# BMS_24.net
KiCad netlist of a schematic drawn in EAGLE
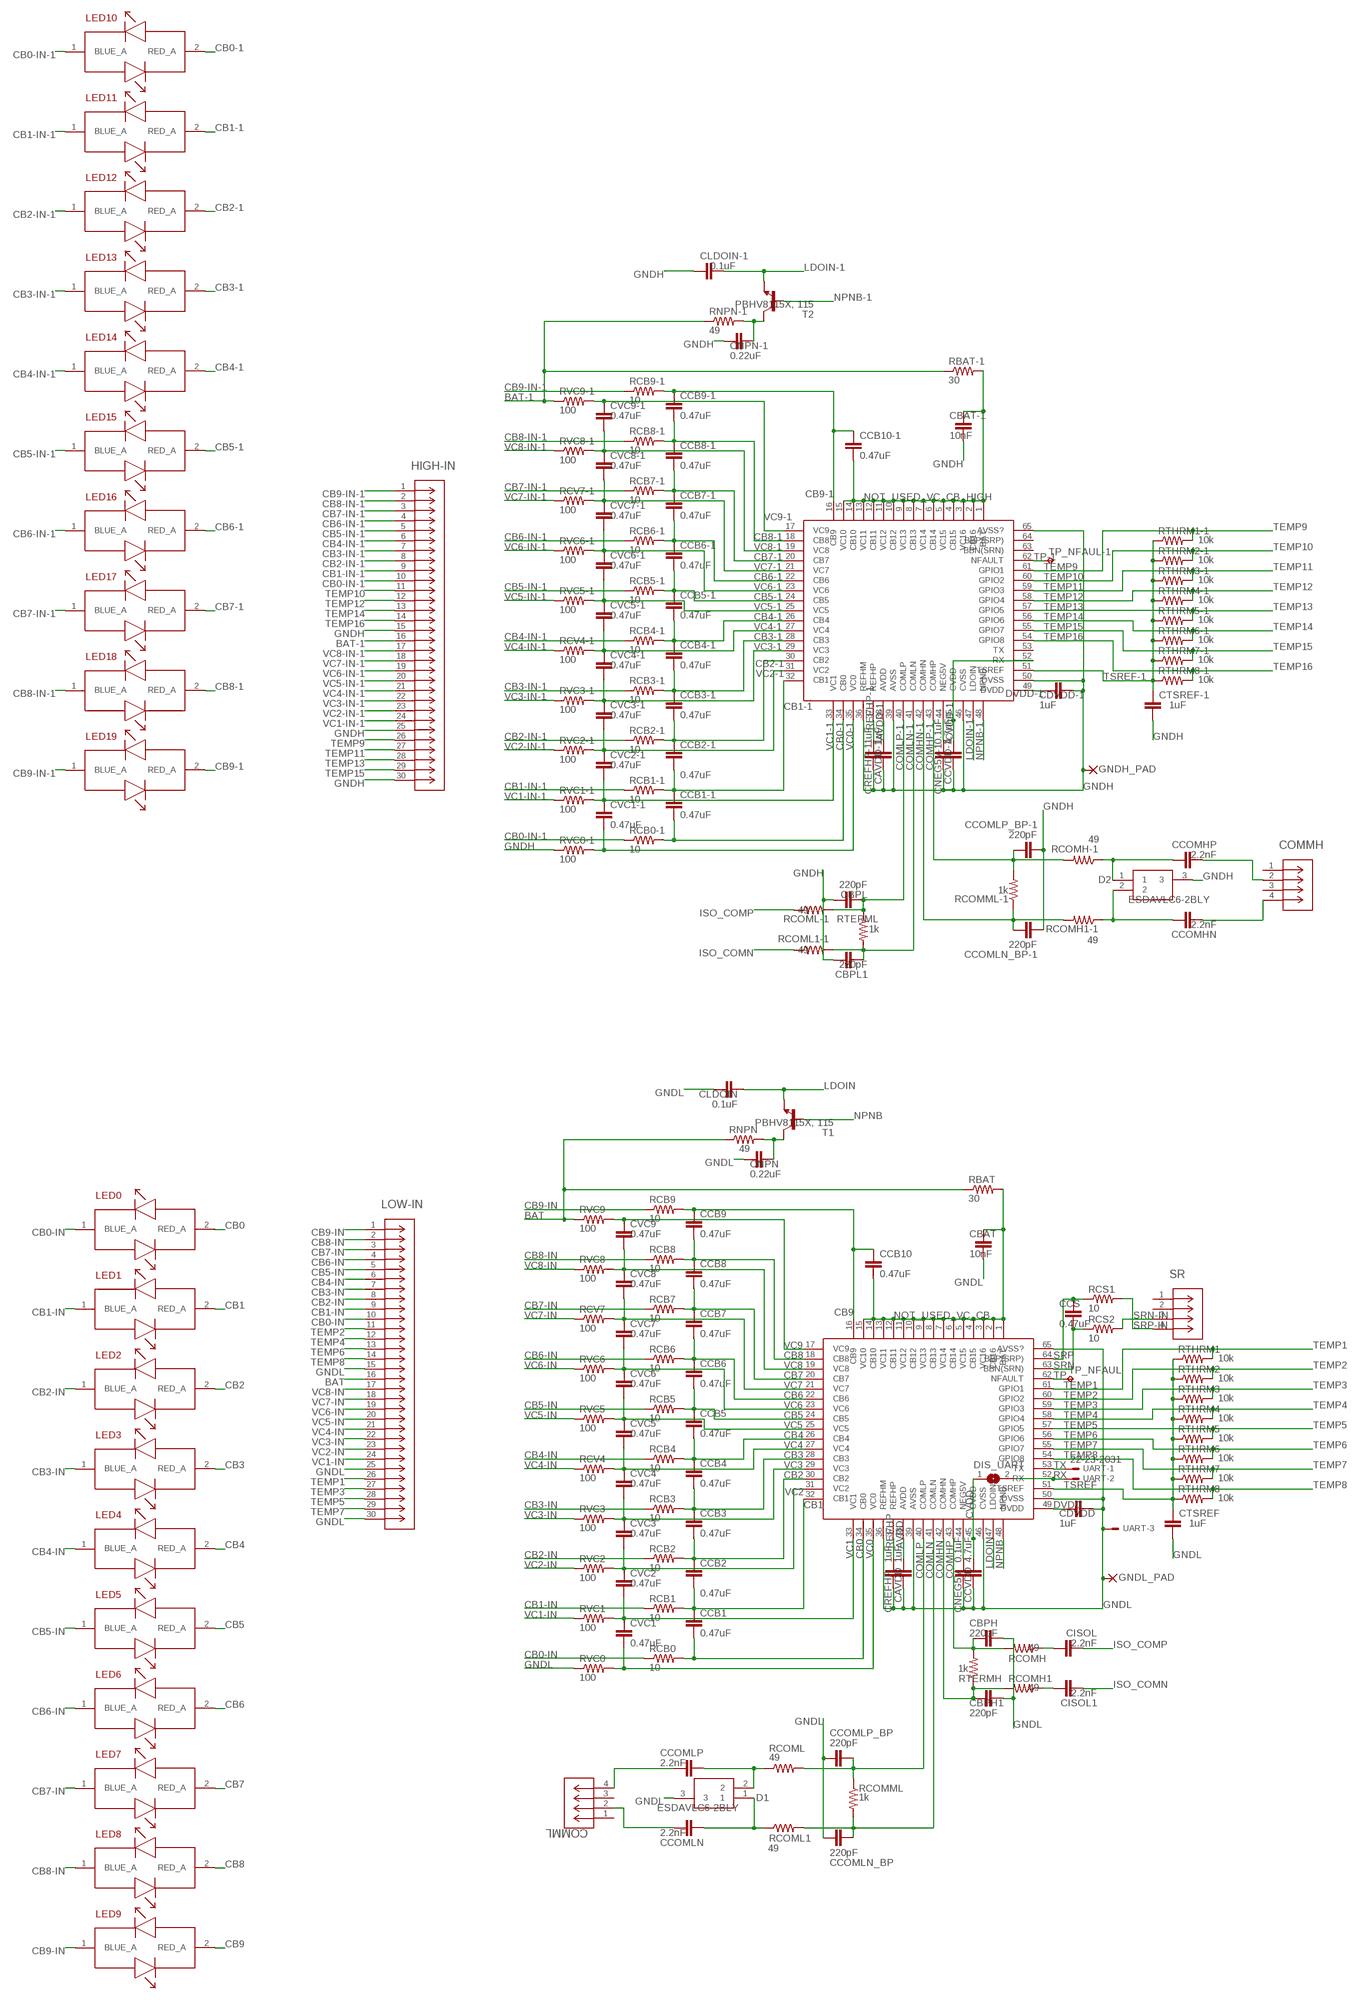
[diagram p0: schematic, sheet 1]

(export (version "E")
  (design (tool "Eeschema 10.0.6"))
  (components
    (comp (ref "CAVDD")
      (value "1uF")
      (footprint "eagle-import:C0603")
      (libsource (lib "eagle-import") (part "CAPACITORC0603"))
    )
    (comp (ref "CAVDD-1")
      (value "1uF")
      (footprint "eagle-import:C0603")
      (libsource (lib "eagle-import") (part "CAPACITORC0603"))
    )
    (comp (ref "CBAT")
      (value "10nF")
      (footprint "eagle-import:C0603")
      (libsource (lib "eagle-import") (part "CAPACITORC0603"))
    )
    (comp (ref "CBAT-1")
      (value "10nF")
      (footprint "eagle-import:C0603")
      (libsource (lib "eagle-import") (part "CAPACITORC0603"))
    )
    (comp (ref "CBPH")
      (value "220pF")
      (footprint "eagle-import:C0603")
      (libsource (lib "eagle-import") (part "CAPACITORC0603"))
    )
    (comp (ref "CBPH1")
      (value "220pF")
      (footprint "eagle-import:C0603")
      (libsource (lib "eagle-import") (part "CAPACITORC0603"))
    )
    (comp (ref "CBPL")
      (value "220pF")
      (footprint "eagle-import:C0603")
      (libsource (lib "eagle-import") (part "CAPACITORC0603"))
    )
    (comp (ref "CBPL1")
      (value "220pF")
      (footprint "eagle-import:C0603")
      (libsource (lib "eagle-import") (part "CAPACITORC0603"))
    )
    (comp (ref "CCB1")
      (value "0.47uF")
      (footprint "eagle-import:C0603")
      (libsource (lib "eagle-import") (part "CAPACITORC0603"))
    )
    (comp (ref "CCB1-1")
      (value "0.47uF")
      (footprint "eagle-import:C0603")
      (libsource (lib "eagle-import") (part "CAPACITORC0603"))
    )
    (comp (ref "CCB2")
      (value "0.47uF")
      (footprint "eagle-import:C0603")
      (libsource (lib "eagle-import") (part "CAPACITORC0603"))
    )
    (comp (ref "CCB2-1")
      (value "0.47uF")
      (footprint "eagle-import:C0603")
      (libsource (lib "eagle-import") (part "CAPACITORC0603"))
    )
    (comp (ref "CCB3")
      (value "0.47uF")
      (footprint "eagle-import:C0603")
      (libsource (lib "eagle-import") (part "CAPACITORC0603"))
    )
    (comp (ref "CCB3-1")
      (value "0.47uF")
      (footprint "eagle-import:C0603")
      (libsource (lib "eagle-import") (part "CAPACITORC0603"))
    )
    (comp (ref "CCB4")
      (value "0.47uF")
      (footprint "eagle-import:C0603")
      (libsource (lib "eagle-import") (part "CAPACITORC0603"))
    )
    (comp (ref "CCB4-1")
      (value "0.47uF")
      (footprint "eagle-import:C0603")
      (libsource (lib "eagle-import") (part "CAPACITORC0603"))
    )
    (comp (ref "CCB5")
      (value "0.47uF")
      (footprint "eagle-import:C0603")
      (libsource (lib "eagle-import") (part "CAPACITORC0603"))
    )
    (comp (ref "CCB5-1")
      (value "0.47uF")
      (footprint "eagle-import:C0603")
      (libsource (lib "eagle-import") (part "CAPACITORC0603"))
    )
    (comp (ref "CCB6")
      (value "0.47uF")
      (footprint "eagle-import:C0603")
      (libsource (lib "eagle-import") (part "CAPACITORC0603"))
    )
    (comp (ref "CCB6-1")
      (value "0.47uF")
      (footprint "eagle-import:C0603")
      (libsource (lib "eagle-import") (part "CAPACITORC0603"))
    )
    (comp (ref "CCB7")
      (value "0.47uF")
      (footprint "eagle-import:C0603")
      (libsource (lib "eagle-import") (part "CAPACITORC0603"))
    )
    (comp (ref "CCB7-1")
      (value "0.47uF")
      (footprint "eagle-import:C0603")
      (libsource (lib "eagle-import") (part "CAPACITORC0603"))
    )
    (comp (ref "CCB8")
      (value "0.47uF")
      (footprint "eagle-import:C0603")
      (libsource (lib "eagle-import") (part "CAPACITORC0603"))
    )
    (comp (ref "CCB8-1")
      (value "0.47uF")
      (footprint "eagle-import:C0603")
      (libsource (lib "eagle-import") (part "CAPACITORC0603"))
    )
    (comp (ref "CCB9")
      (value "0.47uF")
      (footprint "eagle-import:C0603")
      (libsource (lib "eagle-import") (part "CAPACITORC0603"))
    )
    (comp (ref "CCB9-1")
      (value "0.47uF")
      (footprint "eagle-import:C0603")
      (libsource (lib "eagle-import") (part "CAPACITORC0603"))
    )
    (comp (ref "CCB10")
      (value "0.47uF")
      (footprint "eagle-import:C0603")
      (libsource (lib "eagle-import") (part "CAPACITORC0603"))
    )
    (comp (ref "CCB10-1")
      (value "0.47uF")
      (footprint "eagle-import:C0603")
      (libsource (lib "eagle-import") (part "CAPACITORC0603"))
    )
    (comp (ref "CCOMHN")
      (value "2.2nF")
      (footprint "eagle-import:C0603")
      (libsource (lib "eagle-import") (part "CAPACITORC0603"))
    )
    (comp (ref "CCOMHP")
      (value "2.2nF")
      (footprint "eagle-import:C0603")
      (libsource (lib "eagle-import") (part "CAPACITORC0603"))
    )
    (comp (ref "CCOMLN")
      (value "2.2nF")
      (footprint "eagle-import:C0603")
      (libsource (lib "eagle-import") (part "CAPACITORC0603"))
    )
    (comp (ref "CCOMLN_BP")
      (value "220pF")
      (footprint "eagle-import:C0603")
      (libsource (lib "eagle-import") (part "CAPACITORC0603"))
    )
    (comp (ref "CCOMLN_BP-1")
      (value "220pF")
      (footprint "eagle-import:C0603")
      (libsource (lib "eagle-import") (part "CAPACITORC0603"))
    )
    (comp (ref "CCOMLP")
      (value "2.2nF")
      (footprint "eagle-import:C0603")
      (libsource (lib "eagle-import") (part "CAPACITORC0603"))
    )
    (comp (ref "CCOMLP_BP")
      (value "220pF")
      (footprint "eagle-import:C0603")
      (libsource (lib "eagle-import") (part "CAPACITORC0603"))
    )
    (comp (ref "CCOMLP_BP-1")
      (value "220pF")
      (footprint "eagle-import:C0603")
      (libsource (lib "eagle-import") (part "CAPACITORC0603"))
    )
    (comp (ref "CCS")
      (value "0.47uF")
      (footprint "eagle-import:C0603")
      (libsource (lib "eagle-import") (part "CAPACITORC0603"))
    )
    (comp (ref "CCVDD")
      (value "4.7uF")
      (footprint "eagle-import:C0603")
      (libsource (lib "eagle-import") (part "CAPACITORC0603"))
    )
    (comp (ref "CCVDD-1")
      (value "4.7uF")
      (footprint "eagle-import:C0603")
      (libsource (lib "eagle-import") (part "CAPACITORC0603"))
    )
    (comp (ref "CDVDD")
      (value "1uF")
      (footprint "eagle-import:C0603")
      (libsource (lib "eagle-import") (part "CAPACITORC0603"))
    )
    (comp (ref "CDVDD-1")
      (value "1uF")
      (footprint "eagle-import:C0603")
      (libsource (lib "eagle-import") (part "CAPACITORC0603"))
    )
    (comp (ref "CISOL")
      (value "2.2nF")
      (footprint "eagle-import:C0603")
      (libsource (lib "eagle-import") (part "CAPACITORC0603"))
    )
    (comp (ref "CISOL1")
      (value "2.2nF")
      (footprint "eagle-import:C0603")
      (libsource (lib "eagle-import") (part "CAPACITORC0603"))
    )
    (comp (ref "CLDOIN")
      (value "0.1uF")
      (footprint "eagle-import:C0603")
      (libsource (lib "eagle-import") (part "CAPACITORC0603"))
    )
    (comp (ref "CLDOIN-1")
      (value "0.1uF")
      (footprint "eagle-import:C0603")
      (libsource (lib "eagle-import") (part "CAPACITORC0603"))
    )
    (comp (ref "CNEG5V")
      (value "0.1uF")
      (footprint "eagle-import:C0603")
      (libsource (lib "eagle-import") (part "CAPACITORC0603"))
    )
    (comp (ref "CNEG5V-1")
      (value "0.1uF")
      (footprint "eagle-import:C0603")
      (libsource (lib "eagle-import") (part "CAPACITORC0603"))
    )
    (comp (ref "CNPN")
      (value "0.22uF")
      (footprint "eagle-import:C0603")
      (libsource (lib "eagle-import") (part "CAPACITORC0603"))
    )
    (comp (ref "CNPN-1")
      (value "0.22uF")
      (footprint "eagle-import:C0603")
      (libsource (lib "eagle-import") (part "CAPACITORC0603"))
    )
    (comp (ref "COMMH")
      (value "DF11-4DP-2DSA(24)")
      (footprint "eagle-import:CON4_2X2_UF_DF11_HIR")
      (fields (field (name "COPYRIGHT") "Copyright (C) 2023 Ultra Librarian. All rights reserved."))
      (libsource (lib "eagle-import") (part "DF11-4DP-2DSA(24)"))
    )
    (comp (ref "COMML")
      (value "DF11-4DP-2DSA(24)")
      (footprint "eagle-import:CON4_2X2_UF_DF11_HIR")
      (fields (field (name "COPYRIGHT") "Copyright (C) 2023 Ultra Librarian. All rights reserved."))
      (libsource (lib "eagle-import") (part "DF11-4DP-2DSA(24)"))
    )
    (comp (ref "CREFHP")
      (value "1uF")
      (footprint "eagle-import:C0603")
      (libsource (lib "eagle-import") (part "CAPACITORC0603"))
    )
    (comp (ref "CREFHP-1")
      (value "1uF")
      (footprint "eagle-import:C0603")
      (libsource (lib "eagle-import") (part "CAPACITORC0603"))
    )
    (comp (ref "CTSREF")
      (value "1uF")
      (footprint "eagle-import:C0603")
      (libsource (lib "eagle-import") (part "CAPACITORC0603"))
    )
    (comp (ref "CTSREF-1")
      (value "1uF")
      (footprint "eagle-import:C0603")
      (libsource (lib "eagle-import") (part "CAPACITORC0603"))
    )
    (comp (ref "CVC1")
      (value "0.47uF")
      (footprint "eagle-import:C0603")
      (libsource (lib "eagle-import") (part "CAPACITORC0603"))
    )
    (comp (ref "CVC1-1")
      (value "0.47uF")
      (footprint "eagle-import:C0603")
      (libsource (lib "eagle-import") (part "CAPACITORC0603"))
    )
    (comp (ref "CVC2")
      (value "0.47uF")
      (footprint "eagle-import:C0603")
      (libsource (lib "eagle-import") (part "CAPACITORC0603"))
    )
    (comp (ref "CVC2-1")
      (value "0.47uF")
      (footprint "eagle-import:C0603")
      (libsource (lib "eagle-import") (part "CAPACITORC0603"))
    )
    (comp (ref "CVC3")
      (value "0.47uF")
      (footprint "eagle-import:C0603")
      (libsource (lib "eagle-import") (part "CAPACITORC0603"))
    )
    (comp (ref "CVC3-1")
      (value "0.47uF")
      (footprint "eagle-import:C0603")
      (libsource (lib "eagle-import") (part "CAPACITORC0603"))
    )
    (comp (ref "CVC4")
      (value "0.47uF")
      (footprint "eagle-import:C0603")
      (libsource (lib "eagle-import") (part "CAPACITORC0603"))
    )
    (comp (ref "CVC4-1")
      (value "0.47uF")
      (footprint "eagle-import:C0603")
      (libsource (lib "eagle-import") (part "CAPACITORC0603"))
    )
    (comp (ref "CVC5")
      (value "0.47uF")
      (footprint "eagle-import:C0603")
      (libsource (lib "eagle-import") (part "CAPACITORC0603"))
    )
    (comp (ref "CVC5-1")
      (value "0.47uF")
      (footprint "eagle-import:C0603")
      (libsource (lib "eagle-import") (part "CAPACITORC0603"))
    )
    (comp (ref "CVC6")
      (value "0.47uF")
      (footprint "eagle-import:C0603")
      (libsource (lib "eagle-import") (part "CAPACITORC0603"))
    )
    (comp (ref "CVC6-1")
      (value "0.47uF")
      (footprint "eagle-import:C0603")
      (libsource (lib "eagle-import") (part "CAPACITORC0603"))
    )
    (comp (ref "CVC7")
      (value "0.47uF")
      (footprint "eagle-import:C0603")
      (libsource (lib "eagle-import") (part "CAPACITORC0603"))
    )
    (comp (ref "CVC7-1")
      (value "0.47uF")
      (footprint "eagle-import:C0603")
      (libsource (lib "eagle-import") (part "CAPACITORC0603"))
    )
    (comp (ref "CVC8")
      (value "0.47uF")
      (footprint "eagle-import:C0603")
      (libsource (lib "eagle-import") (part "CAPACITORC0603"))
    )
    (comp (ref "CVC8-1")
      (value "0.47uF")
      (footprint "eagle-import:C0603")
      (libsource (lib "eagle-import") (part "CAPACITORC0603"))
    )
    (comp (ref "CVC9")
      (value "0.47uF")
      (footprint "eagle-import:C0603")
      (libsource (lib "eagle-import") (part "CAPACITORC0603"))
    )
    (comp (ref "CVC9-1")
      (value "0.47uF")
      (footprint "eagle-import:C0603")
      (libsource (lib "eagle-import") (part "CAPACITORC0603"))
    )
    (comp (ref "D1")
      (value "ESDAVLC6-2BLY")
      (footprint "eagle-import:SOT95P255X150-3N")
      (fields (field (name "MOUSER_PART_NUMBER") "511-ESDAVLC6-2BLY"))
      (libsource (lib "eagle-import") (part "ESDAVLC6-2BLY"))
    )
    (comp (ref "D2")
      (value "ESDAVLC6-2BLY")
      (footprint "eagle-import:SOT95P255X150-3N")
      (fields (field (name "MOUSER_PART_NUMBER") "511-ESDAVLC6-2BLY"))
      (libsource (lib "eagle-import") (part "ESDAVLC6-2BLY"))
    )
    (comp (ref "DIS_UART")
      (value "SJ")
      (footprint "eagle-import:SJ")
      (libsource (lib "eagle-import") (part "SJ"))
    )
    (comp (ref "GNDH_PAD")
      (value "SMD2")
      (footprint "eagle-import:SMD1,27-2,54")
      (libsource (lib "eagle-import") (part "SMD2"))
    )
    (comp (ref "GNDL_PAD")
      (value "SMD2")
      (footprint "eagle-import:SMD1,27-2,54")
      (libsource (lib "eagle-import") (part "SMD2"))
    )
    (comp (ref "HIGH-IN")
      (value "87606-315LF")
      (footprint "eagle-import:87606-315LF_AMP")
      (fields (field (name "COPYRIGHT") "Copyright (C) 2024 Ultra Librarian. All rights reserved."))
      (libsource (lib "eagle-import") (part "87606-315LF"))
    )
    (comp (ref "IC1")
      (value "PBQ79656PAPTQ1")
      (footprint "eagle-import:QFP50P1200X1200X120-65N")
      (libsource (lib "eagle-import") (part "PBQ79656PAPTQ1"))
    )
    (comp (ref "IC2")
      (value "PBQ79656PAPTQ1")
      (footprint "eagle-import:QFP50P1200X1200X120-65N")
      (libsource (lib "eagle-import") (part "PBQ79656PAPTQ1"))
    )
    (comp (ref "LED0")
      (value "TJ-S1608SW6TNPGLCRB-A5")
      (footprint "eagle-import:TJ-S1608SW6TNPGLCRB-A5")
      (libsource (lib "eagle-import") (part "TJ-S1608SW6TNPGLCRB-A5"))
    )
    (comp (ref "LED1")
      (value "TJ-S1608SW6TNPGLCRB-A5")
      (footprint "eagle-import:TJ-S1608SW6TNPGLCRB-A5")
      (libsource (lib "eagle-import") (part "TJ-S1608SW6TNPGLCRB-A5"))
    )
    (comp (ref "LED2")
      (value "TJ-S1608SW6TNPGLCRB-A5")
      (footprint "eagle-import:TJ-S1608SW6TNPGLCRB-A5")
      (libsource (lib "eagle-import") (part "TJ-S1608SW6TNPGLCRB-A5"))
    )
    (comp (ref "LED3")
      (value "TJ-S1608SW6TNPGLCRB-A5")
      (footprint "eagle-import:TJ-S1608SW6TNPGLCRB-A5")
      (libsource (lib "eagle-import") (part "TJ-S1608SW6TNPGLCRB-A5"))
    )
    (comp (ref "LED4")
      (value "TJ-S1608SW6TNPGLCRB-A5")
      (footprint "eagle-import:TJ-S1608SW6TNPGLCRB-A5")
      (libsource (lib "eagle-import") (part "TJ-S1608SW6TNPGLCRB-A5"))
    )
    (comp (ref "LED5")
      (value "TJ-S1608SW6TNPGLCRB-A5")
      (footprint "eagle-import:TJ-S1608SW6TNPGLCRB-A5")
      (libsource (lib "eagle-import") (part "TJ-S1608SW6TNPGLCRB-A5"))
    )
    (comp (ref "LED6")
      (value "TJ-S1608SW6TNPGLCRB-A5")
      (footprint "eagle-import:TJ-S1608SW6TNPGLCRB-A5")
      (libsource (lib "eagle-import") (part "TJ-S1608SW6TNPGLCRB-A5"))
    )
    (comp (ref "LED7")
      (value "TJ-S1608SW6TNPGLCRB-A5")
      (footprint "eagle-import:TJ-S1608SW6TNPGLCRB-A5")
      (libsource (lib "eagle-import") (part "TJ-S1608SW6TNPGLCRB-A5"))
    )
    (comp (ref "LED8")
      (value "TJ-S1608SW6TNPGLCRB-A5")
      (footprint "eagle-import:TJ-S1608SW6TNPGLCRB-A5")
      (libsource (lib "eagle-import") (part "TJ-S1608SW6TNPGLCRB-A5"))
    )
    (comp (ref "LED9")
      (value "TJ-S1608SW6TNPGLCRB-A5")
      (footprint "eagle-import:TJ-S1608SW6TNPGLCRB-A5")
      (libsource (lib "eagle-import") (part "TJ-S1608SW6TNPGLCRB-A5"))
    )
    (comp (ref "LED10")
      (value "TJ-S1608SW6TNPGLCRB-A5")
      (footprint "eagle-import:TJ-S1608SW6TNPGLCRB-A5")
      (libsource (lib "eagle-import") (part "TJ-S1608SW6TNPGLCRB-A5"))
    )
    (comp (ref "LED11")
      (value "TJ-S1608SW6TNPGLCRB-A5")
      (footprint "eagle-import:TJ-S1608SW6TNPGLCRB-A5")
      (libsource (lib "eagle-import") (part "TJ-S1608SW6TNPGLCRB-A5"))
    )
    (comp (ref "LED12")
      (value "TJ-S1608SW6TNPGLCRB-A5")
      (footprint "eagle-import:TJ-S1608SW6TNPGLCRB-A5")
      (libsource (lib "eagle-import") (part "TJ-S1608SW6TNPGLCRB-A5"))
    )
    (comp (ref "LED13")
      (value "TJ-S1608SW6TNPGLCRB-A5")
      (footprint "eagle-import:TJ-S1608SW6TNPGLCRB-A5")
      (libsource (lib "eagle-import") (part "TJ-S1608SW6TNPGLCRB-A5"))
    )
    (comp (ref "LED14")
      (value "TJ-S1608SW6TNPGLCRB-A5")
      (footprint "eagle-import:TJ-S1608SW6TNPGLCRB-A5")
      (libsource (lib "eagle-import") (part "TJ-S1608SW6TNPGLCRB-A5"))
    )
    (comp (ref "LED15")
      (value "TJ-S1608SW6TNPGLCRB-A5")
      (footprint "eagle-import:TJ-S1608SW6TNPGLCRB-A5")
      (libsource (lib "eagle-import") (part "TJ-S1608SW6TNPGLCRB-A5"))
    )
    (comp (ref "LED16")
      (value "TJ-S1608SW6TNPGLCRB-A5")
      (footprint "eagle-import:TJ-S1608SW6TNPGLCRB-A5")
      (libsource (lib "eagle-import") (part "TJ-S1608SW6TNPGLCRB-A5"))
    )
    (comp (ref "LED17")
      (value "TJ-S1608SW6TNPGLCRB-A5")
      (footprint "eagle-import:TJ-S1608SW6TNPGLCRB-A5")
      (libsource (lib "eagle-import") (part "TJ-S1608SW6TNPGLCRB-A5"))
    )
    (comp (ref "LED18")
      (value "TJ-S1608SW6TNPGLCRB-A5")
      (footprint "eagle-import:TJ-S1608SW6TNPGLCRB-A5")
      (libsource (lib "eagle-import") (part "TJ-S1608SW6TNPGLCRB-A5"))
    )
    (comp (ref "LED19")
      (value "TJ-S1608SW6TNPGLCRB-A5")
      (footprint "eagle-import:TJ-S1608SW6TNPGLCRB-A5")
      (libsource (lib "eagle-import") (part "TJ-S1608SW6TNPGLCRB-A5"))
    )
    (comp (ref "LOW-IN")
      (value "87606-315LF")
      (footprint "eagle-import:87606-315LF_AMP")
      (fields (field (name "COPYRIGHT") "Copyright (C) 2024 Ultra Librarian. All rights reserved."))
      (libsource (lib "eagle-import") (part "87606-315LF"))
    )
    (comp (ref "RBAT")
      (value "30")
      (footprint "eagle-import:R0603")
      (libsource (lib "eagle-import") (part "RESISTORR0603"))
    )
    (comp (ref "RBAT-1")
      (value "30")
      (footprint "eagle-import:R0603")
      (libsource (lib "eagle-import") (part "RESISTORR0603"))
    )
    (comp (ref "RCB0")
      (value "10")
      (footprint "eagle-import:R1210")
      (libsource (lib "eagle-import") (part "R-US_R1210"))
    )
    (comp (ref "RCB0-1")
      (value "10")
      (footprint "eagle-import:R1210")
      (libsource (lib "eagle-import") (part "R-US_R1210"))
    )
    (comp (ref "RCB1")
      (value "10")
      (footprint "eagle-import:R1210")
      (libsource (lib "eagle-import") (part "R-US_R1210"))
    )
    (comp (ref "RCB1-1")
      (value "10")
      (footprint "eagle-import:R1210")
      (libsource (lib "eagle-import") (part "R-US_R1210"))
    )
    (comp (ref "RCB2")
      (value "10")
      (footprint "eagle-import:R1210")
      (libsource (lib "eagle-import") (part "R-US_R1210"))
    )
    (comp (ref "RCB2-1")
      (value "10")
      (footprint "eagle-import:R1210")
      (libsource (lib "eagle-import") (part "R-US_R1210"))
    )
    (comp (ref "RCB3")
      (value "10")
      (footprint "eagle-import:R1210")
      (libsource (lib "eagle-import") (part "R-US_R1210"))
    )
    (comp (ref "RCB3-1")
      (value "10")
      (footprint "eagle-import:R1210")
      (libsource (lib "eagle-import") (part "R-US_R1210"))
    )
    (comp (ref "RCB4")
      (value "10")
      (footprint "eagle-import:R1210")
      (libsource (lib "eagle-import") (part "R-US_R1210"))
    )
    (comp (ref "RCB4-1")
      (value "10")
      (footprint "eagle-import:R1210")
      (libsource (lib "eagle-import") (part "R-US_R1210"))
    )
    (comp (ref "RCB5")
      (value "10")
      (footprint "eagle-import:R1210")
      (libsource (lib "eagle-import") (part "R-US_R1210"))
    )
    (comp (ref "RCB5-1")
      (value "10")
      (footprint "eagle-import:R1210")
      (libsource (lib "eagle-import") (part "R-US_R1210"))
    )
    (comp (ref "RCB6")
      (value "10")
      (footprint "eagle-import:R1210")
      (libsource (lib "eagle-import") (part "R-US_R1210"))
    )
    (comp (ref "RCB6-1")
      (value "10")
      (footprint "eagle-import:R1210")
      (libsource (lib "eagle-import") (part "R-US_R1210"))
    )
    (comp (ref "RCB7")
      (value "10")
      (footprint "eagle-import:R1210")
      (libsource (lib "eagle-import") (part "R-US_R1210"))
    )
    (comp (ref "RCB7-1")
      (value "10")
      (footprint "eagle-import:R1210")
      (libsource (lib "eagle-import") (part "R-US_R1210"))
    )
    (comp (ref "RCB8")
      (value "10")
      (footprint "eagle-import:R1210")
      (libsource (lib "eagle-import") (part "R-US_R1210"))
    )
    (comp (ref "RCB8-1")
      (value "10")
      (footprint "eagle-import:R1210")
      (libsource (lib "eagle-import") (part "R-US_R1210"))
    )
    (comp (ref "RCB9")
      (value "10")
      (footprint "eagle-import:R1210")
      (libsource (lib "eagle-import") (part "R-US_R1210"))
    )
    (comp (ref "RCB9-1")
      (value "10")
      (footprint "eagle-import:R1210")
      (libsource (lib "eagle-import") (part "R-US_R1210"))
    )
    (comp (ref "RCOMH")
      (value "49")
      (footprint "eagle-import:R0603")
      (libsource (lib "eagle-import") (part "RESISTORR0603"))
    )
    (comp (ref "RCOMH-1")
      (value "49")
      (footprint "eagle-import:R0603")
      (libsource (lib "eagle-import") (part "RESISTORR0603"))
    )
    (comp (ref "RCOMH1")
      (value "49")
      (footprint "eagle-import:R0603")
      (libsource (lib "eagle-import") (part "RESISTORR0603"))
    )
    (comp (ref "RCOMH1-1")
      (value "49")
      (footprint "eagle-import:R0603")
      (libsource (lib "eagle-import") (part "RESISTORR0603"))
    )
    (comp (ref "RCOML")
      (value "49")
      (footprint "eagle-import:R0603")
      (libsource (lib "eagle-import") (part "RESISTORR0603"))
    )
    (comp (ref "RCOML-1")
      (value "49")
      (footprint "eagle-import:R0603")
      (libsource (lib "eagle-import") (part "RESISTORR0603"))
    )
    (comp (ref "RCOML1")
      (value "49")
      (footprint "eagle-import:R0603")
      (libsource (lib "eagle-import") (part "RESISTORR0603"))
    )
    (comp (ref "RCOML1-1")
      (value "49")
      (footprint "eagle-import:R0603")
      (libsource (lib "eagle-import") (part "RESISTORR0603"))
    )
    (comp (ref "RCOMML")
      (value "1k")
      (footprint "eagle-import:R0603")
      (libsource (lib "eagle-import") (part "RESISTORR0603"))
    )
    (comp (ref "RCOMML-1")
      (value "1k")
      (footprint "eagle-import:R0603")
      (libsource (lib "eagle-import") (part "RESISTORR0603"))
    )
    (comp (ref "RCS1")
      (value "10")
      (footprint "eagle-import:R0603")
      (libsource (lib "eagle-import") (part "RESISTORR0603"))
    )
    (comp (ref "RCS2")
      (value "10")
      (footprint "eagle-import:R0603")
      (libsource (lib "eagle-import") (part "RESISTORR0603"))
    )
    (comp (ref "RCV4")
      (value "100")
      (footprint "eagle-import:R0603")
      (libsource (lib "eagle-import") (part "RESISTORR0603"))
    )
    (comp (ref "RCV4-1")
      (value "100")
      (footprint "eagle-import:R0603")
      (libsource (lib "eagle-import") (part "RESISTORR0603"))
    )
    (comp (ref "RCV7")
      (value "100")
      (footprint "eagle-import:R0603")
      (libsource (lib "eagle-import") (part "RESISTORR0603"))
    )
    (comp (ref "RCV7-1")
      (value "100")
      (footprint "eagle-import:R0603")
      (libsource (lib "eagle-import") (part "RESISTORR0603"))
    )
    (comp (ref "RNPN")
      (value "49")
      (footprint "eagle-import:R0603")
      (libsource (lib "eagle-import") (part "RESISTORR0603"))
    )
    (comp (ref "RNPN-1")
      (value "49")
      (footprint "eagle-import:R0603")
      (libsource (lib "eagle-import") (part "RESISTORR0603"))
    )
    (comp (ref "RTERMH")
      (value "1k")
      (footprint "eagle-import:R0603")
      (libsource (lib "eagle-import") (part "RESISTORR0603"))
    )
    (comp (ref "RTERML")
      (value "1k")
      (footprint "eagle-import:R0603")
      (libsource (lib "eagle-import") (part "RESISTORR0603"))
    )
    (comp (ref "RTHRM1")
      (value "10k")
      (footprint "eagle-import:R0603")
      (libsource (lib "eagle-import") (part "RESISTORR0603"))
    )
    (comp (ref "RTHRM1-1")
      (value "10k")
      (footprint "eagle-import:R0603")
      (libsource (lib "eagle-import") (part "RESISTORR0603"))
    )
    (comp (ref "RTHRM2")
      (value "10k")
      (footprint "eagle-import:R0603")
      (libsource (lib "eagle-import") (part "RESISTORR0603"))
    )
    (comp (ref "RTHRM2-1")
      (value "10k")
      (footprint "eagle-import:R0603")
      (libsource (lib "eagle-import") (part "RESISTORR0603"))
    )
    (comp (ref "RTHRM3")
      (value "10k")
      (footprint "eagle-import:R0603")
      (libsource (lib "eagle-import") (part "RESISTORR0603"))
    )
    (comp (ref "RTHRM3-1")
      (value "10k")
      (footprint "eagle-import:R0603")
      (libsource (lib "eagle-import") (part "RESISTORR0603"))
    )
    (comp (ref "RTHRM4")
      (value "10k")
      (footprint "eagle-import:R0603")
      (libsource (lib "eagle-import") (part "RESISTORR0603"))
    )
    (comp (ref "RTHRM4-1")
      (value "10k")
      (footprint "eagle-import:R0603")
      (libsource (lib "eagle-import") (part "RESISTORR0603"))
    )
    (comp (ref "RTHRM5")
      (value "10k")
      (footprint "eagle-import:R0603")
      (libsource (lib "eagle-import") (part "RESISTORR0603"))
    )
    (comp (ref "RTHRM5-1")
      (value "10k")
      (footprint "eagle-import:R0603")
      (libsource (lib "eagle-import") (part "RESISTORR0603"))
    )
    (comp (ref "RTHRM6")
      (value "10k")
      (footprint "eagle-import:R0603")
      (libsource (lib "eagle-import") (part "RESISTORR0603"))
    )
    (comp (ref "RTHRM6-1")
      (value "10k")
      (footprint "eagle-import:R0603")
      (libsource (lib "eagle-import") (part "RESISTORR0603"))
    )
    (comp (ref "RTHRM7")
      (value "10k")
      (footprint "eagle-import:R0603")
      (libsource (lib "eagle-import") (part "RESISTORR0603"))
    )
    (comp (ref "RTHRM7-1")
      (value "10k")
      (footprint "eagle-import:R0603")
      (libsource (lib "eagle-import") (part "RESISTORR0603"))
    )
    (comp (ref "RTHRM8")
      (value "10k")
      (footprint "eagle-import:R0603")
      (libsource (lib "eagle-import") (part "RESISTORR0603"))
    )
    (comp (ref "RTHRM8-1")
      (value "10k")
      (footprint "eagle-import:R0603")
      (libsource (lib "eagle-import") (part "RESISTORR0603"))
    )
    (comp (ref "RVC0")
      (value "100")
      (footprint "eagle-import:R0603")
      (libsource (lib "eagle-import") (part "RESISTORR0603"))
    )
    (comp (ref "RVC0-1")
      (value "100")
      (footprint "eagle-import:R0603")
      (libsource (lib "eagle-import") (part "RESISTORR0603"))
    )
    (comp (ref "RVC1")
      (value "100")
      (footprint "eagle-import:R0603")
      (libsource (lib "eagle-import") (part "RESISTORR0603"))
    )
    (comp (ref "RVC1-1")
      (value "100")
      (footprint "eagle-import:R0603")
      (libsource (lib "eagle-import") (part "RESISTORR0603"))
    )
    (comp (ref "RVC2")
      (value "100")
      (footprint "eagle-import:R0603")
      (libsource (lib "eagle-import") (part "RESISTORR0603"))
    )
    (comp (ref "RVC2-1")
      (value "100")
      (footprint "eagle-import:R0603")
      (libsource (lib "eagle-import") (part "RESISTORR0603"))
    )
    (comp (ref "RVC3")
      (value "100")
      (footprint "eagle-import:R0603")
      (libsource (lib "eagle-import") (part "RESISTORR0603"))
    )
    (comp (ref "RVC3-1")
      (value "100")
      (footprint "eagle-import:R0603")
      (libsource (lib "eagle-import") (part "RESISTORR0603"))
    )
    (comp (ref "RVC5")
      (value "100")
      (footprint "eagle-import:R0603")
      (libsource (lib "eagle-import") (part "RESISTORR0603"))
    )
    (comp (ref "RVC5-1")
      (value "100")
      (footprint "eagle-import:R0603")
      (libsource (lib "eagle-import") (part "RESISTORR0603"))
    )
    (comp (ref "RVC6")
      (value "100")
      (footprint "eagle-import:R0603")
      (libsource (lib "eagle-import") (part "RESISTORR0603"))
    )
    (comp (ref "RVC6-1")
      (value "100")
      (footprint "eagle-import:R0603")
      (libsource (lib "eagle-import") (part "RESISTORR0603"))
    )
    (comp (ref "RVC8")
      (value "100")
      (footprint "eagle-import:R0603")
      (libsource (lib "eagle-import") (part "RESISTORR0603"))
    )
    (comp (ref "RVC8-1")
      (value "100")
      (footprint "eagle-import:R0603")
      (libsource (lib "eagle-import") (part "RESISTORR0603"))
    )
    (comp (ref "RVC9")
      (value "100")
      (footprint "eagle-import:R0603")
      (libsource (lib "eagle-import") (part "RESISTORR0603"))
    )
    (comp (ref "RVC9-1")
      (value "100")
      (footprint "eagle-import:R0603")
      (libsource (lib "eagle-import") (part "RESISTORR0603"))
    )
    (comp (ref "SR")
      (value "DF11-4DP-2DSA(24)")
      (footprint "eagle-import:CON4_2X2_UF_DF11_HIR")
      (fields (field (name "COPYRIGHT") "Copyright (C) 2023 Ultra Librarian. All rights reserved."))
      (libsource (lib "eagle-import") (part "DF11-4DP-2DSA(24)"))
    )
    (comp (ref "T1")
      (value "PBHV8115X, 115")
      (footprint "eagle-import:SOT89-BCE")
      (libsource (lib "eagle-import") (part "-NPN-SOT89-BCEBC868"))
    )
    (comp (ref "T2")
      (value "PBHV8115X, 115")
      (footprint "eagle-import:SOT89-BCE")
      (libsource (lib "eagle-import") (part "-NPN-SOT89-BCEBC868"))
    )
    (comp (ref "TP_NFAUL")
      (value "TPB2,54")
      (footprint "eagle-import:B2,54")
      (libsource (lib "eagle-import") (part "TPB2,54"))
    )
    (comp (ref "TP_NFAUL-1")
      (value "TPB2,54")
      (footprint "eagle-import:B2,54")
      (libsource (lib "eagle-import") (part "TPB2,54"))
    )
    (comp (ref "UART")
      (value "22-23-2031")
      (footprint "eagle-import:22-23-2031")
      (fields (field (name "MF") "MOLEX"))
      (libsource (lib "eagle-import") (part "22-23-2031"))
    )
  )
  (nets
    (net (code "1") (name "/AVDD") (class "Default")
      (node (ref "CAVDD") (pin "1") (pinfunction "1_1") (pintype "passive"))
      (node (ref "IC2") (pin "38") (pinfunction "AVDD_38") (pintype "bidirectional"))
    )
    (net (code "2") (name "/AVDD-1") (class "Default")
      (node (ref "CAVDD-1") (pin "1") (pinfunction "1_1") (pintype "passive"))
      (node (ref "IC1") (pin "38") (pinfunction "AVDD_38") (pintype "bidirectional"))
    )
    (net (code "3") (name "/BAT") (class "Default")
      (node (ref "LOW-IN") (pin "16") (pinfunction "16_16") (pintype "passive"))
      (node (ref "RBAT") (pin "1") (pinfunction "1_1") (pintype "passive"))
      (node (ref "RNPN") (pin "1") (pinfunction "1_1") (pintype "passive"))
      (node (ref "RVC9") (pin "1") (pinfunction "1_1") (pintype "passive"))
    )
    (net (code "4") (name "/BAT-1") (class "Default")
      (node (ref "HIGH-IN") (pin "16") (pinfunction "16_16") (pintype "passive"))
      (node (ref "RBAT-1") (pin "1") (pinfunction "1_1") (pintype "passive"))
      (node (ref "RNPN-1") (pin "1") (pinfunction "1_1") (pintype "passive"))
      (node (ref "RVC9-1") (pin "1") (pinfunction "1_1") (pintype "passive"))
    )
    (net (code "5") (name "/CB0") (class "Default")
      (node (ref "CCB1") (pin "2") (pinfunction "2_2") (pintype "passive"))
      (node (ref "IC2") (pin "34") (pinfunction "CB0_34") (pintype "bidirectional"))
      (node (ref "LED0") (pin "2") (pinfunction "RED_A_2") (pintype "bidirectional"))
      (node (ref "RCB0") (pin "2") (pinfunction "2_2") (pintype "passive"))
    )
    (net (code "6") (name "/CB0-1") (class "Default")
      (node (ref "CCB1-1") (pin "2") (pinfunction "2_2") (pintype "passive"))
      (node (ref "IC1") (pin "34") (pinfunction "CB0_34") (pintype "bidirectional"))
      (node (ref "LED10") (pin "2") (pinfunction "RED_A_2") (pintype "bidirectional"))
      (node (ref "RCB0-1") (pin "2") (pinfunction "2_2") (pintype "passive"))
    )
    (net (code "7") (name "/CB0-IN") (class "Default")
      (node (ref "LED0") (pin "1") (pinfunction "BLUE_A_1") (pintype "bidirectional"))
      (node (ref "LOW-IN") (pin "10") (pinfunction "10_10") (pintype "passive"))
      (node (ref "RCB0") (pin "1") (pinfunction "1_1") (pintype "passive"))
    )
    (net (code "8") (name "/CB0-IN-1") (class "Default")
      (node (ref "HIGH-IN") (pin "10") (pinfunction "10_10") (pintype "passive"))
      (node (ref "LED10") (pin "1") (pinfunction "BLUE_A_1") (pintype "bidirectional"))
      (node (ref "RCB0-1") (pin "1") (pinfunction "1_1") (pintype "passive"))
    )
    (net (code "9") (name "/CB1") (class "Default")
      (node (ref "CCB1") (pin "1") (pinfunction "1_1") (pintype "passive"))
      (node (ref "CCB2") (pin "2") (pinfunction "2_2") (pintype "passive"))
      (node (ref "IC2") (pin "32") (pinfunction "CB1_32") (pintype "bidirectional"))
      (node (ref "LED1") (pin "2") (pinfunction "RED_A_2") (pintype "bidirectional"))
      (node (ref "RCB1") (pin "2") (pinfunction "2_2") (pintype "passive"))
    )
    (net (code "10") (name "/CB1-1") (class "Default")
      (node (ref "CCB1-1") (pin "1") (pinfunction "1_1") (pintype "passive"))
      (node (ref "CCB2-1") (pin "2") (pinfunction "2_2") (pintype "passive"))
      (node (ref "IC1") (pin "32") (pinfunction "CB1_32") (pintype "bidirectional"))
      (node (ref "LED11") (pin "2") (pinfunction "RED_A_2") (pintype "bidirectional"))
      (node (ref "RCB1-1") (pin "2") (pinfunction "2_2") (pintype "passive"))
    )
    (net (code "11") (name "/CB1-IN") (class "Default")
      (node (ref "LED1") (pin "1") (pinfunction "BLUE_A_1") (pintype "bidirectional"))
      (node (ref "LOW-IN") (pin "9") (pinfunction "9_9") (pintype "passive"))
      (node (ref "RCB1") (pin "1") (pinfunction "1_1") (pintype "passive"))
    )
    (net (code "12") (name "/CB1-IN-1") (class "Default")
      (node (ref "HIGH-IN") (pin "9") (pinfunction "9_9") (pintype "passive"))
      (node (ref "LED11") (pin "1") (pinfunction "BLUE_A_1") (pintype "bidirectional"))
      (node (ref "RCB1-1") (pin "1") (pinfunction "1_1") (pintype "passive"))
    )
    (net (code "13") (name "/CB2") (class "Default")
      (node (ref "CCB2") (pin "1") (pinfunction "1_1") (pintype "passive"))
      (node (ref "CCB3") (pin "2") (pinfunction "2_2") (pintype "passive"))
      (node (ref "IC2") (pin "30") (pinfunction "CB2_30") (pintype "bidirectional"))
      (node (ref "LED2") (pin "2") (pinfunction "RED_A_2") (pintype "bidirectional"))
      (node (ref "RCB2") (pin "2") (pinfunction "2_2") (pintype "passive"))
    )
    (net (code "14") (name "/CB2-1") (class "Default")
      (node (ref "CCB2-1") (pin "1") (pinfunction "1_1") (pintype "passive"))
      (node (ref "CCB3-1") (pin "2") (pinfunction "2_2") (pintype "passive"))
      (node (ref "IC1") (pin "30") (pinfunction "CB2_30") (pintype "bidirectional"))
      (node (ref "LED12") (pin "2") (pinfunction "RED_A_2") (pintype "bidirectional"))
      (node (ref "RCB2-1") (pin "2") (pinfunction "2_2") (pintype "passive"))
    )
    (net (code "15") (name "/CB2-IN") (class "Default")
      (node (ref "LED2") (pin "1") (pinfunction "BLUE_A_1") (pintype "bidirectional"))
      (node (ref "LOW-IN") (pin "8") (pinfunction "8_8") (pintype "passive"))
      (node (ref "RCB2") (pin "1") (pinfunction "1_1") (pintype "passive"))
    )
    (net (code "16") (name "/CB2-IN-1") (class "Default")
      (node (ref "HIGH-IN") (pin "8") (pinfunction "8_8") (pintype "passive"))
      (node (ref "LED12") (pin "1") (pinfunction "BLUE_A_1") (pintype "bidirectional"))
      (node (ref "RCB2-1") (pin "1") (pinfunction "1_1") (pintype "passive"))
    )
    (net (code "17") (name "/CB3") (class "Default")
      (node (ref "CCB3") (pin "1") (pinfunction "1_1") (pintype "passive"))
      (node (ref "CCB4") (pin "2") (pinfunction "2_2") (pintype "passive"))
      (node (ref "IC2") (pin "28") (pinfunction "CB3_28") (pintype "bidirectional"))
      (node (ref "LED3") (pin "2") (pinfunction "RED_A_2") (pintype "bidirectional"))
      (node (ref "RCB3") (pin "2") (pinfunction "2_2") (pintype "passive"))
    )
    (net (code "18") (name "/CB3-1") (class "Default")
      (node (ref "CCB3-1") (pin "1") (pinfunction "1_1") (pintype "passive"))
      (node (ref "CCB4-1") (pin "2") (pinfunction "2_2") (pintype "passive"))
      (node (ref "IC1") (pin "28") (pinfunction "CB3_28") (pintype "bidirectional"))
      (node (ref "LED13") (pin "2") (pinfunction "RED_A_2") (pintype "bidirectional"))
      (node (ref "RCB3-1") (pin "2") (pinfunction "2_2") (pintype "passive"))
    )
    (net (code "19") (name "/CB3-IN") (class "Default")
      (node (ref "LED3") (pin "1") (pinfunction "BLUE_A_1") (pintype "bidirectional"))
      (node (ref "LOW-IN") (pin "7") (pinfunction "7_7") (pintype "passive"))
      (node (ref "RCB3") (pin "1") (pinfunction "1_1") (pintype "passive"))
    )
    (net (code "20") (name "/CB3-IN-1") (class "Default")
      (node (ref "HIGH-IN") (pin "7") (pinfunction "7_7") (pintype "passive"))
      (node (ref "LED13") (pin "1") (pinfunction "BLUE_A_1") (pintype "bidirectional"))
      (node (ref "RCB3-1") (pin "1") (pinfunction "1_1") (pintype "passive"))
    )
    (net (code "21") (name "/CB4") (class "Default")
      (node (ref "CCB4") (pin "1") (pinfunction "1_1") (pintype "passive"))
      (node (ref "CCB5") (pin "2") (pinfunction "2_2") (pintype "passive"))
      (node (ref "IC2") (pin "26") (pinfunction "CB4_26") (pintype "bidirectional"))
      (node (ref "LED4") (pin "2") (pinfunction "RED_A_2") (pintype "bidirectional"))
      (node (ref "RCB4") (pin "2") (pinfunction "2_2") (pintype "passive"))
    )
    (net (code "22") (name "/CB4-1") (class "Default")
      (node (ref "CCB4-1") (pin "1") (pinfunction "1_1") (pintype "passive"))
      (node (ref "CCB5-1") (pin "2") (pinfunction "2_2") (pintype "passive"))
      (node (ref "IC1") (pin "26") (pinfunction "CB4_26") (pintype "bidirectional"))
      (node (ref "LED14") (pin "2") (pinfunction "RED_A_2") (pintype "bidirectional"))
      (node (ref "RCB4-1") (pin "2") (pinfunction "2_2") (pintype "passive"))
    )
    (net (code "23") (name "/CB4-IN") (class "Default")
      (node (ref "LED4") (pin "1") (pinfunction "BLUE_A_1") (pintype "bidirectional"))
      (node (ref "LOW-IN") (pin "6") (pinfunction "6_6") (pintype "passive"))
      (node (ref "RCB4") (pin "1") (pinfunction "1_1") (pintype "passive"))
    )
    (net (code "24") (name "/CB4-IN-1") (class "Default")
      (node (ref "HIGH-IN") (pin "6") (pinfunction "6_6") (pintype "passive"))
      (node (ref "LED14") (pin "1") (pinfunction "BLUE_A_1") (pintype "bidirectional"))
      (node (ref "RCB4-1") (pin "1") (pinfunction "1_1") (pintype "passive"))
    )
    (net (code "25") (name "/CB5") (class "Default")
      (node (ref "CCB5") (pin "1") (pinfunction "1_1") (pintype "passive"))
      (node (ref "CCB6") (pin "2") (pinfunction "2_2") (pintype "passive"))
      (node (ref "IC2") (pin "24") (pinfunction "CB5_24") (pintype "bidirectional"))
      (node (ref "LED5") (pin "2") (pinfunction "RED_A_2") (pintype "bidirectional"))
      (node (ref "RCB5") (pin "2") (pinfunction "2_2") (pintype "passive"))
    )
    (net (code "26") (name "/CB5-1") (class "Default")
      (node (ref "CCB5-1") (pin "1") (pinfunction "1_1") (pintype "passive"))
      (node (ref "CCB6-1") (pin "2") (pinfunction "2_2") (pintype "passive"))
      (node (ref "IC1") (pin "24") (pinfunction "CB5_24") (pintype "bidirectional"))
      (node (ref "LED15") (pin "2") (pinfunction "RED_A_2") (pintype "bidirectional"))
      (node (ref "RCB5-1") (pin "2") (pinfunction "2_2") (pintype "passive"))
    )
    (net (code "27") (name "/CB5-IN") (class "Default")
      (node (ref "LED5") (pin "1") (pinfunction "BLUE_A_1") (pintype "bidirectional"))
      (node (ref "LOW-IN") (pin "5") (pinfunction "5_5") (pintype "passive"))
      (node (ref "RCB5") (pin "1") (pinfunction "1_1") (pintype "passive"))
    )
    (net (code "28") (name "/CB5-IN-1") (class "Default")
      (node (ref "HIGH-IN") (pin "5") (pinfunction "5_5") (pintype "passive"))
      (node (ref "LED15") (pin "1") (pinfunction "BLUE_A_1") (pintype "bidirectional"))
      (node (ref "RCB5-1") (pin "1") (pinfunction "1_1") (pintype "passive"))
    )
    (net (code "29") (name "/CB6") (class "Default")
      (node (ref "CCB6") (pin "1") (pinfunction "1_1") (pintype "passive"))
      (node (ref "CCB7") (pin "2") (pinfunction "2_2") (pintype "passive"))
      (node (ref "IC2") (pin "22") (pinfunction "CB6_22") (pintype "bidirectional"))
      (node (ref "LED6") (pin "2") (pinfunction "RED_A_2") (pintype "bidirectional"))
      (node (ref "RCB6") (pin "2") (pinfunction "2_2") (pintype "passive"))
    )
    (net (code "30") (name "/CB6-1") (class "Default")
      (node (ref "CCB6-1") (pin "1") (pinfunction "1_1") (pintype "passive"))
      (node (ref "CCB7-1") (pin "2") (pinfunction "2_2") (pintype "passive"))
      (node (ref "IC1") (pin "22") (pinfunction "CB6_22") (pintype "bidirectional"))
      (node (ref "LED16") (pin "2") (pinfunction "RED_A_2") (pintype "bidirectional"))
      (node (ref "RCB6-1") (pin "2") (pinfunction "2_2") (pintype "passive"))
    )
    (net (code "31") (name "/CB6-IN") (class "Default")
      (node (ref "LED6") (pin "1") (pinfunction "BLUE_A_1") (pintype "bidirectional"))
      (node (ref "LOW-IN") (pin "4") (pinfunction "4_4") (pintype "passive"))
      (node (ref "RCB6") (pin "1") (pinfunction "1_1") (pintype "passive"))
    )
    (net (code "32") (name "/CB6-IN-1") (class "Default")
      (node (ref "HIGH-IN") (pin "4") (pinfunction "4_4") (pintype "passive"))
      (node (ref "LED16") (pin "1") (pinfunction "BLUE_A_1") (pintype "bidirectional"))
      (node (ref "RCB6-1") (pin "1") (pinfunction "1_1") (pintype "passive"))
    )
    (net (code "33") (name "/CB7") (class "Default")
      (node (ref "CCB7") (pin "1") (pinfunction "1_1") (pintype "passive"))
      (node (ref "CCB8") (pin "2") (pinfunction "2_2") (pintype "passive"))
      (node (ref "IC2") (pin "20") (pinfunction "CB7_20") (pintype "bidirectional"))
      (node (ref "LED7") (pin "2") (pinfunction "RED_A_2") (pintype "bidirectional"))
      (node (ref "RCB7") (pin "2") (pinfunction "2_2") (pintype "passive"))
    )
    (net (code "34") (name "/CB7-1") (class "Default")
      (node (ref "CCB7-1") (pin "1") (pinfunction "1_1") (pintype "passive"))
      (node (ref "CCB8-1") (pin "2") (pinfunction "2_2") (pintype "passive"))
      (node (ref "IC1") (pin "20") (pinfunction "CB7_20") (pintype "bidirectional"))
      (node (ref "LED17") (pin "2") (pinfunction "RED_A_2") (pintype "bidirectional"))
      (node (ref "RCB7-1") (pin "2") (pinfunction "2_2") (pintype "passive"))
    )
    (net (code "35") (name "/CB7-IN") (class "Default")
      (node (ref "LED7") (pin "1") (pinfunction "BLUE_A_1") (pintype "bidirectional"))
      (node (ref "LOW-IN") (pin "3") (pinfunction "3_3") (pintype "passive"))
      (node (ref "RCB7") (pin "1") (pinfunction "1_1") (pintype "passive"))
    )
    (net (code "36") (name "/CB7-IN-1") (class "Default")
      (node (ref "HIGH-IN") (pin "3") (pinfunction "3_3") (pintype "passive"))
      (node (ref "LED17") (pin "1") (pinfunction "BLUE_A_1") (pintype "bidirectional"))
      (node (ref "RCB7-1") (pin "1") (pinfunction "1_1") (pintype "passive"))
    )
    (net (code "37") (name "/CB8") (class "Default")
      (node (ref "CCB8") (pin "1") (pinfunction "1_1") (pintype "passive"))
      (node (ref "CCB9") (pin "2") (pinfunction "2_2") (pintype "passive"))
      (node (ref "IC2") (pin "18") (pinfunction "CB8_18") (pintype "bidirectional"))
      (node (ref "LED8") (pin "2") (pinfunction "RED_A_2") (pintype "bidirectional"))
      (node (ref "RCB8") (pin "2") (pinfunction "2_2") (pintype "passive"))
    )
    (net (code "38") (name "/CB8-1") (class "Default")
      (node (ref "CCB8-1") (pin "1") (pinfunction "1_1") (pintype "passive"))
      (node (ref "CCB9-1") (pin "2") (pinfunction "2_2") (pintype "passive"))
      (node (ref "IC1") (pin "18") (pinfunction "CB8_18") (pintype "bidirectional"))
      (node (ref "LED18") (pin "2") (pinfunction "RED_A_2") (pintype "bidirectional"))
      (node (ref "RCB8-1") (pin "2") (pinfunction "2_2") (pintype "passive"))
    )
    (net (code "39") (name "/CB8-IN") (class "Default")
      (node (ref "LED8") (pin "1") (pinfunction "BLUE_A_1") (pintype "bidirectional"))
      (node (ref "LOW-IN") (pin "2") (pinfunction "2_2") (pintype "passive"))
      (node (ref "RCB8") (pin "1") (pinfunction "1_1") (pintype "passive"))
    )
    (net (code "40") (name "/CB8-IN-1") (class "Default")
      (node (ref "HIGH-IN") (pin "2") (pinfunction "2_2") (pintype "passive"))
      (node (ref "LED18") (pin "1") (pinfunction "BLUE_A_1") (pintype "bidirectional"))
      (node (ref "RCB8-1") (pin "1") (pinfunction "1_1") (pintype "passive"))
    )
    (net (code "41") (name "/CB9") (class "Default")
      (node (ref "CCB10") (pin "2") (pinfunction "2_2") (pintype "passive"))
      (node (ref "CCB9") (pin "1") (pinfunction "1_1") (pintype "passive"))
      (node (ref "IC2") (pin "16") (pinfunction "CB9_16") (pintype "bidirectional"))
      (node (ref "LED9") (pin "2") (pinfunction "RED_A_2") (pintype "bidirectional"))
      (node (ref "RCB9") (pin "2") (pinfunction "2_2") (pintype "passive"))
    )
    (net (code "42") (name "/CB9-1") (class "Default")
      (node (ref "CCB10-1") (pin "2") (pinfunction "2_2") (pintype "passive"))
      (node (ref "CCB9-1") (pin "1") (pinfunction "1_1") (pintype "passive"))
      (node (ref "IC1") (pin "16") (pinfunction "CB9_16") (pintype "bidirectional"))
      (node (ref "LED19") (pin "2") (pinfunction "RED_A_2") (pintype "bidirectional"))
      (node (ref "RCB9-1") (pin "2") (pinfunction "2_2") (pintype "passive"))
    )
    (net (code "43") (name "/CB9-IN") (class "Default")
      (node (ref "LED9") (pin "1") (pinfunction "BLUE_A_1") (pintype "bidirectional"))
      (node (ref "LOW-IN") (pin "1") (pinfunction "1_1") (pintype "passive"))
      (node (ref "RCB9") (pin "1") (pinfunction "1_1") (pintype "passive"))
    )
    (net (code "44") (name "/CB9-IN-1") (class "Default")
      (node (ref "HIGH-IN") (pin "1") (pinfunction "1_1") (pintype "passive"))
      (node (ref "LED19") (pin "1") (pinfunction "BLUE_A_1") (pintype "bidirectional"))
      (node (ref "RCB9-1") (pin "1") (pinfunction "1_1") (pintype "passive"))
    )
    (net (code "45") (name "/COMHN") (class "Default")
      (node (ref "CBPH1") (pin "1") (pinfunction "1_1") (pintype "passive"))
      (node (ref "IC2") (pin "42") (pinfunction "COMHN_42") (pintype "bidirectional"))
      (node (ref "RCOMH1") (pin "2") (pinfunction "2_2") (pintype "passive"))
      (node (ref "RTERMH") (pin "1") (pinfunction "1_1") (pintype "passive"))
    )
    (net (code "46") (name "/COMHN-1") (class "Default")
      (node (ref "CCOMLN_BP-1") (pin "1") (pinfunction "1_1") (pintype "passive"))
      (node (ref "IC1") (pin "42") (pinfunction "COMHN_42") (pintype "bidirectional"))
      (node (ref "RCOMH1-1") (pin "2") (pinfunction "2_2") (pintype "passive"))
      (node (ref "RCOMML-1") (pin "1") (pinfunction "1_1") (pintype "passive"))
    )
    (net (code "47") (name "/COMHP") (class "Default")
      (node (ref "CBPH") (pin "1") (pinfunction "1_1") (pintype "passive"))
      (node (ref "IC2") (pin "43") (pinfunction "COMHP_43") (pintype "bidirectional"))
      (node (ref "RCOMH") (pin "2") (pinfunction "2_2") (pintype "passive"))
      (node (ref "RTERMH") (pin "2") (pinfunction "2_2") (pintype "passive"))
    )
    (net (code "48") (name "/COMHP-1") (class "Default")
      (node (ref "CCOMLP_BP-1") (pin "1") (pinfunction "1_1") (pintype "passive"))
      (node (ref "IC1") (pin "43") (pinfunction "COMHP_43") (pintype "bidirectional"))
      (node (ref "RCOMH-1") (pin "2") (pinfunction "2_2") (pintype "passive"))
      (node (ref "RCOMML-1") (pin "2") (pinfunction "2_2") (pintype "passive"))
    )
    (net (code "49") (name "/COMLN") (class "Default")
      (node (ref "CCOMLN_BP") (pin "1") (pinfunction "1_1") (pintype "passive"))
      (node (ref "IC2") (pin "41") (pinfunction "COMLN_41") (pintype "bidirectional"))
      (node (ref "RCOML1") (pin "2") (pinfunction "2_2") (pintype "passive"))
      (node (ref "RCOMML") (pin "2") (pinfunction "2_2") (pintype "passive"))
    )
    (net (code "50") (name "/COMLN-1") (class "Default")
      (node (ref "CBPL1") (pin "1") (pinfunction "1_1") (pintype "passive"))
      (node (ref "IC1") (pin "41") (pinfunction "COMLN_41") (pintype "bidirectional"))
      (node (ref "RCOML1-1") (pin "2") (pinfunction "2_2") (pintype "passive"))
      (node (ref "RTERML") (pin "2") (pinfunction "2_2") (pintype "passive"))
    )
    (net (code "51") (name "/COMLP") (class "Default")
      (node (ref "CCOMLP_BP") (pin "1") (pinfunction "1_1") (pintype "passive"))
      (node (ref "IC2") (pin "40") (pinfunction "COMLP_40") (pintype "bidirectional"))
      (node (ref "RCOML") (pin "2") (pinfunction "2_2") (pintype "passive"))
      (node (ref "RCOMML") (pin "1") (pinfunction "1_1") (pintype "passive"))
    )
    (net (code "52") (name "/COMLP-1") (class "Default")
      (node (ref "CBPL") (pin "1") (pinfunction "1_1") (pintype "passive"))
      (node (ref "IC1") (pin "40") (pinfunction "COMLP_40") (pintype "bidirectional"))
      (node (ref "RCOML-1") (pin "2") (pinfunction "2_2") (pintype "passive"))
      (node (ref "RTERML") (pin "1") (pinfunction "1_1") (pintype "passive"))
    )
    (net (code "53") (name "/CVDD") (class "Default")
      (node (ref "CCVDD") (pin "1") (pinfunction "1_1") (pintype "passive"))
      (node (ref "DIS_UART") (pin "1") (pinfunction "1_1") (pintype "passive"))
      (node (ref "IC2") (pin "45") (pinfunction "CVDD_45") (pintype "bidirectional"))
    )
    (net (code "54") (name "/CVDD-1") (class "Default")
      (node (ref "CCVDD-1") (pin "1") (pinfunction "1_1") (pintype "passive"))
      (node (ref "IC1") (pin "45") (pinfunction "CVDD_45") (pintype "bidirectional"))
      (node (ref "IC1") (pin "52") (pinfunction "RX_52") (pintype "bidirectional"))
    )
    (net (code "55") (name "/DVDD") (class "Default")
      (node (ref "CDVDD") (pin "1") (pinfunction "1_1") (pintype "passive"))
      (node (ref "IC2") (pin "49") (pinfunction "DVDD_49") (pintype "bidirectional"))
    )
    (net (code "56") (name "/DVDD-1") (class "Default")
      (node (ref "CDVDD-1") (pin "1") (pinfunction "1_1") (pintype "passive"))
      (node (ref "IC1") (pin "49") (pinfunction "DVDD_49") (pintype "bidirectional"))
    )
    (net (code "57") (name "/GNDH") (class "Default")
      (node (ref "CAVDD-1") (pin "2") (pinfunction "2_2") (pintype "passive"))
      (node (ref "CBAT-1") (pin "1") (pinfunction "1_1") (pintype "passive"))
      (node (ref "CBPL") (pin "2") (pinfunction "2_2") (pintype "passive"))
      (node (ref "CBPL1") (pin "2") (pinfunction "2_2") (pintype "passive"))
      (node (ref "CCOMLN_BP-1") (pin "2") (pinfunction "2_2") (pintype "passive"))
      (node (ref "CCOMLP_BP-1") (pin "2") (pinfunction "2_2") (pintype "passive"))
      (node (ref "CCVDD-1") (pin "2") (pinfunction "2_2") (pintype "passive"))
      (node (ref "CDVDD-1") (pin "2") (pinfunction "2_2") (pintype "passive"))
      (node (ref "CLDOIN-1") (pin "2") (pinfunction "2_2") (pintype "passive"))
      (node (ref "CNEG5V-1") (pin "2") (pinfunction "2_2") (pintype "passive"))
      (node (ref "CNPN-1") (pin "1") (pinfunction "1_1") (pintype "passive"))
      (node (ref "CREFHP-1") (pin "2") (pinfunction "2_2") (pintype "passive"))
      (node (ref "CTSREF-1") (pin "2") (pinfunction "2_2") (pintype "passive"))
      (node (ref "D2") (pin "3") (pinfunction "3_3") (pintype "bidirectional"))
      (node (ref "GNDH_PAD") (pin "1") (pinfunction "P_1") (pintype "passive"))
      (node (ref "HIGH-IN") (pin "15") (pinfunction "15_15") (pintype "passive"))
      (node (ref "HIGH-IN") (pin "25") (pinfunction "25_25") (pintype "passive"))
      (node (ref "HIGH-IN") (pin "30") (pinfunction "30_30") (pintype "passive"))
      (node (ref "IC1") (pin "36") (pinfunction "REFHM_36") (pintype "bidirectional"))
      (node (ref "IC1") (pin "39") (pinfunction "AVSS_39") (pintype "bidirectional"))
      (node (ref "IC1") (pin "46") (pinfunction "CVSS_46") (pintype "bidirectional"))
      (node (ref "IC1") (pin "50") (pinfunction "DVSS_50") (pintype "bidirectional"))
      (node (ref "IC1") (pin "65") (pinfunction "AVSS?_65") (pintype "bidirectional"))
      (node (ref "RVC0-1") (pin "1") (pinfunction "1_1") (pintype "passive"))
    )
    (net (code "58") (name "/GNDL") (class "Default")
      (node (ref "CAVDD") (pin "2") (pinfunction "2_2") (pintype "passive"))
      (node (ref "CBAT") (pin "1") (pinfunction "1_1") (pintype "passive"))
      (node (ref "CBPH") (pin "2") (pinfunction "2_2") (pintype "passive"))
      (node (ref "CBPH1") (pin "2") (pinfunction "2_2") (pintype "passive"))
      (node (ref "CCOMLN_BP") (pin "2") (pinfunction "2_2") (pintype "passive"))
      (node (ref "CCOMLP_BP") (pin "2") (pinfunction "2_2") (pintype "passive"))
      (node (ref "CCVDD") (pin "2") (pinfunction "2_2") (pintype "passive"))
      (node (ref "CDVDD") (pin "2") (pinfunction "2_2") (pintype "passive"))
      (node (ref "CLDOIN") (pin "2") (pinfunction "2_2") (pintype "passive"))
      (node (ref "CNEG5V") (pin "2") (pinfunction "2_2") (pintype "passive"))
      (node (ref "CNPN") (pin "1") (pinfunction "1_1") (pintype "passive"))
      (node (ref "CREFHP") (pin "2") (pinfunction "2_2") (pintype "passive"))
      (node (ref "CTSREF") (pin "2") (pinfunction "2_2") (pintype "passive"))
      (node (ref "D1") (pin "3") (pinfunction "3_3") (pintype "bidirectional"))
      (node (ref "GNDL_PAD") (pin "1") (pinfunction "P_1") (pintype "passive"))
      (node (ref "IC2") (pin "36") (pinfunction "REFHM_36") (pintype "bidirectional"))
      (node (ref "IC2") (pin "39") (pinfunction "AVSS_39") (pintype "bidirectional"))
      (node (ref "IC2") (pin "46") (pinfunction "CVSS_46") (pintype "bidirectional"))
      (node (ref "IC2") (pin "50") (pinfunction "DVSS_50") (pintype "bidirectional"))
      (node (ref "IC2") (pin "65") (pinfunction "AVSS?_65") (pintype "bidirectional"))
      (node (ref "LOW-IN") (pin "15") (pinfunction "15_15") (pintype "passive"))
      (node (ref "LOW-IN") (pin "25") (pinfunction "25_25") (pintype "passive"))
      (node (ref "LOW-IN") (pin "30") (pinfunction "30_30") (pintype "passive"))
      (node (ref "RVC0") (pin "1") (pinfunction "1_1") (pintype "passive"))
      (node (ref "UART") (pin "3") (pinfunction "S_3") (pintype "passive"))
    )
    (net (code "59") (name "/ISO_COMN") (class "Default")
      (node (ref "CISOL1") (pin "1") (pinfunction "1_1") (pintype "passive"))
      (node (ref "RCOML1-1") (pin "1") (pinfunction "1_1") (pintype "passive"))
    )
    (net (code "60") (name "/ISO_COMP") (class "Default")
      (node (ref "CISOL") (pin "1") (pinfunction "1_1") (pintype "passive"))
      (node (ref "RCOML-1") (pin "1") (pinfunction "1_1") (pintype "passive"))
    )
    (net (code "61") (name "/LDOIN") (class "Default")
      (node (ref "CLDOIN") (pin "1") (pinfunction "1_1") (pintype "passive"))
      (node (ref "IC2") (pin "47") (pinfunction "LDOIN_47") (pintype "bidirectional"))
      (node (ref "T1") (pin "E") (pinfunction "E_E") (pintype "passive"))
    )
    (net (code "62") (name "/LDOIN-1") (class "Default")
      (node (ref "CLDOIN-1") (pin "1") (pinfunction "1_1") (pintype "passive"))
      (node (ref "IC1") (pin "47") (pinfunction "LDOIN_47") (pintype "bidirectional"))
      (node (ref "T2") (pin "E") (pinfunction "E_E") (pintype "passive"))
    )
    (net (code "63") (name "/NOT_USED_VC_CB") (class "Default")
      (node (ref "CBAT") (pin "2") (pinfunction "2_2") (pintype "passive"))
      (node (ref "CCB10") (pin "1") (pinfunction "1_1") (pintype "passive"))
      (node (ref "IC2") (pin "1") (pinfunction "BAT_1") (pintype "bidirectional"))
      (node (ref "IC2") (pin "10") (pinfunction "CB12_10") (pintype "bidirectional"))
      (node (ref "IC2") (pin "11") (pinfunction "VC12_11") (pintype "bidirectional"))
      (node (ref "IC2") (pin "12") (pinfunction "CB11_12") (pintype "bidirectional"))
      (node (ref "IC2") (pin "13") (pinfunction "VC11_13") (pintype "bidirectional"))
      (node (ref "IC2") (pin "14") (pinfunction "CB10_14") (pintype "bidirectional"))
      (node (ref "IC2") (pin "15") (pinfunction "VC10_15") (pintype "bidirectional"))
      (node (ref "IC2") (pin "2") (pinfunction "CB16_2") (pintype "bidirectional"))
      (node (ref "IC2") (pin "3") (pinfunction "VC16_3") (pintype "bidirectional"))
      (node (ref "IC2") (pin "4") (pinfunction "CB15_4") (pintype "bidirectional"))
      (node (ref "IC2") (pin "5") (pinfunction "VC15_5") (pintype "bidirectional"))
      (node (ref "IC2") (pin "6") (pinfunction "CB14_6") (pintype "bidirectional"))
      (node (ref "IC2") (pin "7") (pinfunction "VC14_7") (pintype "bidirectional"))
      (node (ref "IC2") (pin "8") (pinfunction "CB13_8") (pintype "bidirectional"))
      (node (ref "IC2") (pin "9") (pinfunction "VC13_9") (pintype "bidirectional"))
      (node (ref "RBAT") (pin "2") (pinfunction "2_2") (pintype "passive"))
    )
    (net (code "64") (name "/NOT_USED_VC_CB_HIGH") (class "Default")
      (node (ref "CBAT-1") (pin "2") (pinfunction "2_2") (pintype "passive"))
      (node (ref "CCB10-1") (pin "1") (pinfunction "1_1") (pintype "passive"))
      (node (ref "IC1") (pin "1") (pinfunction "BAT_1") (pintype "bidirectional"))
      (node (ref "IC1") (pin "10") (pinfunction "CB12_10") (pintype "bidirectional"))
      (node (ref "IC1") (pin "11") (pinfunction "VC12_11") (pintype "bidirectional"))
      (node (ref "IC1") (pin "12") (pinfunction "CB11_12") (pintype "bidirectional"))
      (node (ref "IC1") (pin "13") (pinfunction "VC11_13") (pintype "bidirectional"))
      (node (ref "IC1") (pin "14") (pinfunction "CB10_14") (pintype "bidirectional"))
      (node (ref "IC1") (pin "15") (pinfunction "VC10_15") (pintype "bidirectional"))
      (node (ref "IC1") (pin "2") (pinfunction "CB16_2") (pintype "bidirectional"))
      (node (ref "IC1") (pin "3") (pinfunction "VC16_3") (pintype "bidirectional"))
      (node (ref "IC1") (pin "4") (pinfunction "CB15_4") (pintype "bidirectional"))
      (node (ref "IC1") (pin "5") (pinfunction "VC15_5") (pintype "bidirectional"))
      (node (ref "IC1") (pin "6") (pinfunction "CB14_6") (pintype "bidirectional"))
      (node (ref "IC1") (pin "7") (pinfunction "VC14_7") (pintype "bidirectional"))
      (node (ref "IC1") (pin "8") (pinfunction "CB13_8") (pintype "bidirectional"))
      (node (ref "IC1") (pin "9") (pinfunction "VC13_9") (pintype "bidirectional"))
      (node (ref "RBAT-1") (pin "2") (pinfunction "2_2") (pintype "passive"))
    )
    (net (code "65") (name "/NPNB") (class "Default")
      (node (ref "IC2") (pin "48") (pinfunction "NPNB_48") (pintype "bidirectional"))
      (node (ref "T1") (pin "B") (pinfunction "B_B") (pintype "passive"))
    )
    (net (code "66") (name "/NPNB-1") (class "Default")
      (node (ref "IC1") (pin "48") (pinfunction "NPNB_48") (pintype "bidirectional"))
      (node (ref "T2") (pin "B") (pinfunction "B_B") (pintype "passive"))
    )
    (net (code "67") (name "/REFHP") (class "Default")
      (node (ref "CREFHP") (pin "1") (pinfunction "1_1") (pintype "passive"))
      (node (ref "IC2") (pin "37") (pinfunction "REFHP_37") (pintype "bidirectional"))
    )
    (net (code "68") (name "/REFHP-1") (class "Default")
      (node (ref "CREFHP-1") (pin "1") (pinfunction "1_1") (pintype "passive"))
      (node (ref "IC1") (pin "37") (pinfunction "REFHP_37") (pintype "bidirectional"))
    )
    (net (code "69") (name "/RX") (class "Default")
      (node (ref "DIS_UART") (pin "2") (pinfunction "2_2") (pintype "passive"))
      (node (ref "IC2") (pin "52") (pinfunction "RX_52") (pintype "bidirectional"))
      (node (ref "UART") (pin "2") (pinfunction "S_2") (pintype "passive"))
    )
    (net (code "70") (name "/SRN") (class "Default")
      (node (ref "CCS") (pin "1") (pinfunction "1_1") (pintype "passive"))
      (node (ref "IC2") (pin "63") (pinfunction "BBN(SRN)_63") (pintype "bidirectional"))
      (node (ref "RCS2") (pin "1") (pinfunction "1_1") (pintype "passive"))
    )
    (net (code "71") (name "/SRN-IN") (class "Default")
      (node (ref "RCS2") (pin "2") (pinfunction "2_2") (pintype "passive"))
      (node (ref "SR") (pin "3") (pinfunction "3_3") (pintype "passive"))
    )
    (net (code "72") (name "/SRP") (class "Default")
      (node (ref "CCS") (pin "2") (pinfunction "2_2") (pintype "passive"))
      (node (ref "IC2") (pin "64") (pinfunction "BBP(SRP)_64") (pintype "bidirectional"))
      (node (ref "RCS1") (pin "1") (pinfunction "1_1") (pintype "passive"))
    )
    (net (code "73") (name "/SRP-IN") (class "Default")
      (node (ref "RCS1") (pin "2") (pinfunction "2_2") (pintype "passive"))
      (node (ref "SR") (pin "4") (pinfunction "4_4") (pintype "passive"))
    )
    (net (code "74") (name "/TEMP1") (class "Default")
      (node (ref "IC2") (pin "61") (pinfunction "GPIO1_61") (pintype "bidirectional"))
      (node (ref "LOW-IN") (pin "26") (pinfunction "26_26") (pintype "passive"))
      (node (ref "RTHRM1") (pin "2") (pinfunction "2_2") (pintype "passive"))
    )
    (net (code "75") (name "/TEMP2") (class "Default")
      (node (ref "IC2") (pin "60") (pinfunction "GPIO2_60") (pintype "bidirectional"))
      (node (ref "LOW-IN") (pin "11") (pinfunction "11_11") (pintype "passive"))
      (node (ref "RTHRM2") (pin "2") (pinfunction "2_2") (pintype "passive"))
    )
    (net (code "76") (name "/TEMP3") (class "Default")
      (node (ref "IC2") (pin "59") (pinfunction "GPIO3_59") (pintype "bidirectional"))
      (node (ref "LOW-IN") (pin "27") (pinfunction "27_27") (pintype "passive"))
      (node (ref "RTHRM3") (pin "2") (pinfunction "2_2") (pintype "passive"))
    )
    (net (code "77") (name "/TEMP4") (class "Default")
      (node (ref "IC2") (pin "58") (pinfunction "GPIO4_58") (pintype "bidirectional"))
      (node (ref "LOW-IN") (pin "12") (pinfunction "12_12") (pintype "passive"))
      (node (ref "RTHRM4") (pin "2") (pinfunction "2_2") (pintype "passive"))
    )
    (net (code "78") (name "/TEMP5") (class "Default")
      (node (ref "IC2") (pin "57") (pinfunction "GPIO5_57") (pintype "bidirectional"))
      (node (ref "LOW-IN") (pin "28") (pinfunction "28_28") (pintype "passive"))
      (node (ref "RTHRM5") (pin "2") (pinfunction "2_2") (pintype "passive"))
    )
    (net (code "79") (name "/TEMP6") (class "Default")
      (node (ref "IC2") (pin "56") (pinfunction "GPIO6_56") (pintype "bidirectional"))
      (node (ref "LOW-IN") (pin "13") (pinfunction "13_13") (pintype "passive"))
      (node (ref "RTHRM6") (pin "2") (pinfunction "2_2") (pintype "passive"))
    )
    (net (code "80") (name "/TEMP7") (class "Default")
      (node (ref "IC2") (pin "55") (pinfunction "GPIO7_55") (pintype "bidirectional"))
      (node (ref "LOW-IN") (pin "29") (pinfunction "29_29") (pintype "passive"))
      (node (ref "RTHRM7") (pin "2") (pinfunction "2_2") (pintype "passive"))
    )
    (net (code "81") (name "/TEMP8") (class "Default")
      (node (ref "IC2") (pin "54") (pinfunction "GPIO8_54") (pintype "bidirectional"))
      (node (ref "LOW-IN") (pin "14") (pinfunction "14_14") (pintype "passive"))
      (node (ref "RTHRM8") (pin "2") (pinfunction "2_2") (pintype "passive"))
    )
    (net (code "82") (name "/TEMP9") (class "Default")
      (node (ref "HIGH-IN") (pin "26") (pinfunction "26_26") (pintype "passive"))
      (node (ref "IC1") (pin "61") (pinfunction "GPIO1_61") (pintype "bidirectional"))
      (node (ref "RTHRM1-1") (pin "2") (pinfunction "2_2") (pintype "passive"))
    )
    (net (code "83") (name "/TEMP10") (class "Default")
      (node (ref "HIGH-IN") (pin "11") (pinfunction "11_11") (pintype "passive"))
      (node (ref "IC1") (pin "60") (pinfunction "GPIO2_60") (pintype "bidirectional"))
      (node (ref "RTHRM2-1") (pin "2") (pinfunction "2_2") (pintype "passive"))
    )
    (net (code "84") (name "/TEMP11") (class "Default")
      (node (ref "HIGH-IN") (pin "27") (pinfunction "27_27") (pintype "passive"))
      (node (ref "IC1") (pin "59") (pinfunction "GPIO3_59") (pintype "bidirectional"))
      (node (ref "RTHRM3-1") (pin "2") (pinfunction "2_2") (pintype "passive"))
    )
    (net (code "85") (name "/TEMP12") (class "Default")
      (node (ref "HIGH-IN") (pin "12") (pinfunction "12_12") (pintype "passive"))
      (node (ref "IC1") (pin "58") (pinfunction "GPIO4_58") (pintype "bidirectional"))
      (node (ref "RTHRM4-1") (pin "2") (pinfunction "2_2") (pintype "passive"))
    )
    (net (code "86") (name "/TEMP13") (class "Default")
      (node (ref "HIGH-IN") (pin "28") (pinfunction "28_28") (pintype "passive"))
      (node (ref "IC1") (pin "57") (pinfunction "GPIO5_57") (pintype "bidirectional"))
      (node (ref "RTHRM5-1") (pin "2") (pinfunction "2_2") (pintype "passive"))
    )
    (net (code "87") (name "/TEMP14") (class "Default")
      (node (ref "HIGH-IN") (pin "13") (pinfunction "13_13") (pintype "passive"))
      (node (ref "IC1") (pin "56") (pinfunction "GPIO6_56") (pintype "bidirectional"))
      (node (ref "RTHRM6-1") (pin "2") (pinfunction "2_2") (pintype "passive"))
    )
    (net (code "88") (name "/TEMP15") (class "Default")
      (node (ref "HIGH-IN") (pin "29") (pinfunction "29_29") (pintype "passive"))
      (node (ref "IC1") (pin "55") (pinfunction "GPIO7_55") (pintype "bidirectional"))
      (node (ref "RTHRM7-1") (pin "2") (pinfunction "2_2") (pintype "passive"))
    )
    (net (code "89") (name "/TEMP16") (class "Default")
      (node (ref "HIGH-IN") (pin "14") (pinfunction "14_14") (pintype "passive"))
      (node (ref "IC1") (pin "54") (pinfunction "GPIO8_54") (pintype "bidirectional"))
      (node (ref "RTHRM8-1") (pin "2") (pinfunction "2_2") (pintype "passive"))
    )
    (net (code "90") (name "/TP") (class "Default")
      (node (ref "IC2") (pin "62") (pinfunction "NFAULT_62") (pintype "bidirectional"))
      (node (ref "TP_NFAUL") (pin "TP") (pinfunction "TP_TP") (pintype "input"))
    )
    (net (code "91") (name "/TP-1") (class "Default")
      (node (ref "IC1") (pin "62") (pinfunction "NFAULT_62") (pintype "bidirectional"))
      (node (ref "TP_NFAUL-1") (pin "TP") (pinfunction "TP_TP") (pintype "input"))
    )
    (net (code "92") (name "/TSREF") (class "Default")
      (node (ref "CTSREF") (pin "1") (pinfunction "1_1") (pintype "passive"))
      (node (ref "IC2") (pin "51") (pinfunction "TSREF_51") (pintype "bidirectional"))
      (node (ref "RTHRM1") (pin "1") (pinfunction "1_1") (pintype "passive"))
      (node (ref "RTHRM2") (pin "1") (pinfunction "1_1") (pintype "passive"))
      (node (ref "RTHRM3") (pin "1") (pinfunction "1_1") (pintype "passive"))
      (node (ref "RTHRM4") (pin "1") (pinfunction "1_1") (pintype "passive"))
      (node (ref "RTHRM5") (pin "1") (pinfunction "1_1") (pintype "passive"))
      (node (ref "RTHRM6") (pin "1") (pinfunction "1_1") (pintype "passive"))
      (node (ref "RTHRM7") (pin "1") (pinfunction "1_1") (pintype "passive"))
      (node (ref "RTHRM8") (pin "1") (pinfunction "1_1") (pintype "passive"))
    )
    (net (code "93") (name "/TSREF-1") (class "Default")
      (node (ref "CTSREF-1") (pin "1") (pinfunction "1_1") (pintype "passive"))
      (node (ref "IC1") (pin "51") (pinfunction "TSREF_51") (pintype "bidirectional"))
      (node (ref "RTHRM1-1") (pin "1") (pinfunction "1_1") (pintype "passive"))
      (node (ref "RTHRM2-1") (pin "1") (pinfunction "1_1") (pintype "passive"))
      (node (ref "RTHRM3-1") (pin "1") (pinfunction "1_1") (pintype "passive"))
      (node (ref "RTHRM4-1") (pin "1") (pinfunction "1_1") (pintype "passive"))
      (node (ref "RTHRM5-1") (pin "1") (pinfunction "1_1") (pintype "passive"))
      (node (ref "RTHRM6-1") (pin "1") (pinfunction "1_1") (pintype "passive"))
      (node (ref "RTHRM7-1") (pin "1") (pinfunction "1_1") (pintype "passive"))
      (node (ref "RTHRM8-1") (pin "1") (pinfunction "1_1") (pintype "passive"))
    )
    (net (code "94") (name "/TX") (class "Default")
      (node (ref "IC2") (pin "53") (pinfunction "TX_53") (pintype "bidirectional"))
      (node (ref "UART") (pin "1") (pinfunction "S_1") (pintype "passive"))
    )
    (net (code "95") (name "/VC0") (class "Default")
      (node (ref "CVC1") (pin "2") (pinfunction "2_2") (pintype "passive"))
      (node (ref "IC2") (pin "35") (pinfunction "VC0_35") (pintype "bidirectional"))
      (node (ref "RVC0") (pin "2") (pinfunction "2_2") (pintype "passive"))
    )
    (net (code "96") (name "/VC0-1") (class "Default")
      (node (ref "CVC1-1") (pin "2") (pinfunction "2_2") (pintype "passive"))
      (node (ref "IC1") (pin "35") (pinfunction "VC0_35") (pintype "bidirectional"))
      (node (ref "RVC0-1") (pin "2") (pinfunction "2_2") (pintype "passive"))
    )
    (net (code "97") (name "/VC1") (class "Default")
      (node (ref "CVC1") (pin "1") (pinfunction "1_1") (pintype "passive"))
      (node (ref "CVC2") (pin "2") (pinfunction "2_2") (pintype "passive"))
      (node (ref "IC2") (pin "33") (pinfunction "VC1_33") (pintype "bidirectional"))
      (node (ref "RVC1") (pin "2") (pinfunction "2_2") (pintype "passive"))
    )
    (net (code "98") (name "/VC1-1") (class "Default")
      (node (ref "CVC1-1") (pin "1") (pinfunction "1_1") (pintype "passive"))
      (node (ref "CVC2-1") (pin "2") (pinfunction "2_2") (pintype "passive"))
      (node (ref "IC1") (pin "33") (pinfunction "VC1_33") (pintype "bidirectional"))
      (node (ref "RVC1-1") (pin "2") (pinfunction "2_2") (pintype "passive"))
    )
    (net (code "99") (name "/VC1-IN") (class "Default")
      (node (ref "LOW-IN") (pin "24") (pinfunction "24_24") (pintype "passive"))
      (node (ref "RVC1") (pin "1") (pinfunction "1_1") (pintype "passive"))
    )
    (net (code "100") (name "/VC1-IN-1") (class "Default")
      (node (ref "HIGH-IN") (pin "24") (pinfunction "24_24") (pintype "passive"))
      (node (ref "RVC1-1") (pin "1") (pinfunction "1_1") (pintype "passive"))
    )
    (net (code "101") (name "/VC2") (class "Default")
      (node (ref "CVC2") (pin "1") (pinfunction "1_1") (pintype "passive"))
      (node (ref "CVC3") (pin "2") (pinfunction "2_2") (pintype "passive"))
      (node (ref "IC2") (pin "31") (pinfunction "VC2_31") (pintype "bidirectional"))
      (node (ref "RVC2") (pin "2") (pinfunction "2_2") (pintype "passive"))
    )
    (net (code "102") (name "/VC2-1") (class "Default")
      (node (ref "CVC2-1") (pin "1") (pinfunction "1_1") (pintype "passive"))
      (node (ref "CVC3-1") (pin "2") (pinfunction "2_2") (pintype "passive"))
      (node (ref "IC1") (pin "31") (pinfunction "VC2_31") (pintype "bidirectional"))
      (node (ref "RVC2-1") (pin "2") (pinfunction "2_2") (pintype "passive"))
    )
    (net (code "103") (name "/VC2-IN") (class "Default")
      (node (ref "LOW-IN") (pin "23") (pinfunction "23_23") (pintype "passive"))
      (node (ref "RVC2") (pin "1") (pinfunction "1_1") (pintype "passive"))
    )
    (net (code "104") (name "/VC2-IN-1") (class "Default")
      (node (ref "HIGH-IN") (pin "23") (pinfunction "23_23") (pintype "passive"))
      (node (ref "RVC2-1") (pin "1") (pinfunction "1_1") (pintype "passive"))
    )
    (net (code "105") (name "/VC3") (class "Default")
      (node (ref "CVC3") (pin "1") (pinfunction "1_1") (pintype "passive"))
      (node (ref "CVC4") (pin "2") (pinfunction "2_2") (pintype "passive"))
      (node (ref "IC2") (pin "29") (pinfunction "VC3_29") (pintype "bidirectional"))
      (node (ref "RVC3") (pin "2") (pinfunction "2_2") (pintype "passive"))
    )
    (net (code "106") (name "/VC3-1") (class "Default")
      (node (ref "CVC3-1") (pin "1") (pinfunction "1_1") (pintype "passive"))
      (node (ref "CVC4-1") (pin "2") (pinfunction "2_2") (pintype "passive"))
      (node (ref "IC1") (pin "29") (pinfunction "VC3_29") (pintype "bidirectional"))
      (node (ref "RVC3-1") (pin "2") (pinfunction "2_2") (pintype "passive"))
    )
    (net (code "107") (name "/VC3-IN") (class "Default")
      (node (ref "LOW-IN") (pin "22") (pinfunction "22_22") (pintype "passive"))
      (node (ref "RVC3") (pin "1") (pinfunction "1_1") (pintype "passive"))
    )
    (net (code "108") (name "/VC3-IN-1") (class "Default")
      (node (ref "HIGH-IN") (pin "22") (pinfunction "22_22") (pintype "passive"))
      (node (ref "RVC3-1") (pin "1") (pinfunction "1_1") (pintype "passive"))
    )
    (net (code "109") (name "/VC4") (class "Default")
      (node (ref "CVC4") (pin "1") (pinfunction "1_1") (pintype "passive"))
      (node (ref "CVC5") (pin "2") (pinfunction "2_2") (pintype "passive"))
      (node (ref "IC2") (pin "27") (pinfunction "VC4_27") (pintype "bidirectional"))
      (node (ref "RCV4") (pin "2") (pinfunction "2_2") (pintype "passive"))
    )
    (net (code "110") (name "/VC4-1") (class "Default")
      (node (ref "CVC4-1") (pin "1") (pinfunction "1_1") (pintype "passive"))
      (node (ref "CVC5-1") (pin "2") (pinfunction "2_2") (pintype "passive"))
      (node (ref "IC1") (pin "27") (pinfunction "VC4_27") (pintype "bidirectional"))
      (node (ref "RCV4-1") (pin "2") (pinfunction "2_2") (pintype "passive"))
    )
    (net (code "111") (name "/VC4-IN") (class "Default")
      (node (ref "LOW-IN") (pin "21") (pinfunction "21_21") (pintype "passive"))
      (node (ref "RCV4") (pin "1") (pinfunction "1_1") (pintype "passive"))
    )
    (net (code "112") (name "/VC4-IN-1") (class "Default")
      (node (ref "HIGH-IN") (pin "21") (pinfunction "21_21") (pintype "passive"))
      (node (ref "RCV4-1") (pin "1") (pinfunction "1_1") (pintype "passive"))
    )
    (net (code "113") (name "/VC5") (class "Default")
      (node (ref "CVC5") (pin "1") (pinfunction "1_1") (pintype "passive"))
      (node (ref "CVC6") (pin "2") (pinfunction "2_2") (pintype "passive"))
      (node (ref "IC2") (pin "25") (pinfunction "VC5_25") (pintype "bidirectional"))
      (node (ref "RVC5") (pin "2") (pinfunction "2_2") (pintype "passive"))
    )
    (net (code "114") (name "/VC5-1") (class "Default")
      (node (ref "CVC5-1") (pin "1") (pinfunction "1_1") (pintype "passive"))
      (node (ref "CVC6-1") (pin "2") (pinfunction "2_2") (pintype "passive"))
      (node (ref "IC1") (pin "25") (pinfunction "VC5_25") (pintype "bidirectional"))
      (node (ref "RVC5-1") (pin "2") (pinfunction "2_2") (pintype "passive"))
    )
    (net (code "115") (name "/VC5-IN") (class "Default")
      (node (ref "LOW-IN") (pin "20") (pinfunction "20_20") (pintype "passive"))
      (node (ref "RVC5") (pin "1") (pinfunction "1_1") (pintype "passive"))
    )
    (net (code "116") (name "/VC5-IN-1") (class "Default")
      (node (ref "HIGH-IN") (pin "20") (pinfunction "20_20") (pintype "passive"))
      (node (ref "RVC5-1") (pin "1") (pinfunction "1_1") (pintype "passive"))
    )
    (net (code "117") (name "/VC6") (class "Default")
      (node (ref "CVC6") (pin "1") (pinfunction "1_1") (pintype "passive"))
      (node (ref "CVC7") (pin "2") (pinfunction "2_2") (pintype "passive"))
      (node (ref "IC2") (pin "23") (pinfunction "VC6_23") (pintype "bidirectional"))
      (node (ref "RVC6") (pin "2") (pinfunction "2_2") (pintype "passive"))
    )
    (net (code "118") (name "/VC6-1") (class "Default")
      (node (ref "CVC6-1") (pin "1") (pinfunction "1_1") (pintype "passive"))
      (node (ref "CVC7-1") (pin "2") (pinfunction "2_2") (pintype "passive"))
      (node (ref "IC1") (pin "23") (pinfunction "VC6_23") (pintype "bidirectional"))
      (node (ref "RVC6-1") (pin "2") (pinfunction "2_2") (pintype "passive"))
    )
    (net (code "119") (name "/VC6-IN") (class "Default")
      (node (ref "LOW-IN") (pin "19") (pinfunction "19_19") (pintype "passive"))
      (node (ref "RVC6") (pin "1") (pinfunction "1_1") (pintype "passive"))
    )
    (net (code "120") (name "/VC6-IN-1") (class "Default")
      (node (ref "HIGH-IN") (pin "19") (pinfunction "19_19") (pintype "passive"))
      (node (ref "RVC6-1") (pin "1") (pinfunction "1_1") (pintype "passive"))
    )
    (net (code "121") (name "/VC7") (class "Default")
      (node (ref "CVC7") (pin "1") (pinfunction "1_1") (pintype "passive"))
      (node (ref "CVC8") (pin "2") (pinfunction "2_2") (pintype "passive"))
      (node (ref "IC2") (pin "21") (pinfunction "VC7_21") (pintype "bidirectional"))
      (node (ref "RCV7") (pin "2") (pinfunction "2_2") (pintype "passive"))
    )
    (net (code "122") (name "/VC7-1") (class "Default")
      (node (ref "CVC7-1") (pin "1") (pinfunction "1_1") (pintype "passive"))
      (node (ref "CVC8-1") (pin "2") (pinfunction "2_2") (pintype "passive"))
      (node (ref "IC1") (pin "21") (pinfunction "VC7_21") (pintype "bidirectional"))
      (node (ref "RCV7-1") (pin "2") (pinfunction "2_2") (pintype "passive"))
    )
    (net (code "123") (name "/VC7-IN") (class "Default")
      (node (ref "LOW-IN") (pin "18") (pinfunction "18_18") (pintype "passive"))
      (node (ref "RCV7") (pin "1") (pinfunction "1_1") (pintype "passive"))
    )
    (net (code "124") (name "/VC7-IN-1") (class "Default")
      (node (ref "HIGH-IN") (pin "18") (pinfunction "18_18") (pintype "passive"))
      (node (ref "RCV7-1") (pin "1") (pinfunction "1_1") (pintype "passive"))
    )
    (net (code "125") (name "/VC8") (class "Default")
      (node (ref "CVC8") (pin "1") (pinfunction "1_1") (pintype "passive"))
      (node (ref "CVC9") (pin "2") (pinfunction "2_2") (pintype "passive"))
      (node (ref "IC2") (pin "19") (pinfunction "VC8_19") (pintype "bidirectional"))
      (node (ref "RVC8") (pin "2") (pinfunction "2_2") (pintype "passive"))
    )
    (net (code "126") (name "/VC8-1") (class "Default")
      (node (ref "CVC8-1") (pin "1") (pinfunction "1_1") (pintype "passive"))
      (node (ref "CVC9-1") (pin "2") (pinfunction "2_2") (pintype "passive"))
      (node (ref "IC1") (pin "19") (pinfunction "VC8_19") (pintype "bidirectional"))
      (node (ref "RVC8-1") (pin "2") (pinfunction "2_2") (pintype "passive"))
    )
    (net (code "127") (name "/VC8-IN") (class "Default")
      (node (ref "LOW-IN") (pin "17") (pinfunction "17_17") (pintype "passive"))
      (node (ref "RVC8") (pin "1") (pinfunction "1_1") (pintype "passive"))
    )
    (net (code "128") (name "/VC8-IN-1") (class "Default")
      (node (ref "HIGH-IN") (pin "17") (pinfunction "17_17") (pintype "passive"))
      (node (ref "RVC8-1") (pin "1") (pinfunction "1_1") (pintype "passive"))
    )
    (net (code "129") (name "/VC9") (class "Default")
      (node (ref "CVC9") (pin "1") (pinfunction "1_1") (pintype "passive"))
      (node (ref "IC2") (pin "17") (pinfunction "VC9_17") (pintype "bidirectional"))
      (node (ref "RVC9") (pin "2") (pinfunction "2_2") (pintype "passive"))
    )
    (net (code "130") (name "/VC9-1") (class "Default")
      (node (ref "CVC9-1") (pin "1") (pinfunction "1_1") (pintype "passive"))
      (node (ref "IC1") (pin "17") (pinfunction "VC9_17") (pintype "bidirectional"))
      (node (ref "RVC9-1") (pin "2") (pinfunction "2_2") (pintype "passive"))
    )
    (net (code "131") (name "Net-(CCOMHN-Pad1)") (class "Default")
      (node (ref "CCOMHN") (pin "1") (pinfunction "1_1") (pintype "passive"))
      (node (ref "COMMH") (pin "4") (pinfunction "4_4") (pintype "passive"))
    )
    (net (code "132") (name "Net-(CCOMHN-Pad2)") (class "Default")
      (node (ref "CCOMHN") (pin "2") (pinfunction "2_2") (pintype "passive"))
      (node (ref "D2") (pin "2") (pinfunction "2_2") (pintype "bidirectional"))
      (node (ref "RCOMH1-1") (pin "1") (pinfunction "1_1") (pintype "passive"))
    )
    (net (code "133") (name "Net-(CCOMHP-Pad1)") (class "Default")
      (node (ref "CCOMHP") (pin "1") (pinfunction "1_1") (pintype "passive"))
      (node (ref "COMMH") (pin "2") (pinfunction "2_2") (pintype "passive"))
    )
    (net (code "134") (name "Net-(CCOMHP-Pad2)") (class "Default")
      (node (ref "CCOMHP") (pin "2") (pinfunction "2_2") (pintype "passive"))
      (node (ref "D2") (pin "1") (pinfunction "1_1") (pintype "bidirectional"))
      (node (ref "RCOMH-1") (pin "1") (pinfunction "1_1") (pintype "passive"))
    )
    (net (code "135") (name "Net-(CCOMLN-Pad1)") (class "Default")
      (node (ref "CCOMLN") (pin "1") (pinfunction "1_1") (pintype "passive"))
      (node (ref "COMML") (pin "2") (pinfunction "2_2") (pintype "passive"))
    )
    (net (code "136") (name "Net-(CCOMLN-Pad2)") (class "Default")
      (node (ref "CCOMLN") (pin "2") (pinfunction "2_2") (pintype "passive"))
      (node (ref "D1") (pin "1") (pinfunction "1_1") (pintype "bidirectional"))
      (node (ref "RCOML1") (pin "1") (pinfunction "1_1") (pintype "passive"))
    )
    (net (code "137") (name "Net-(CCOMLP-Pad1)") (class "Default")
      (node (ref "CCOMLP") (pin "1") (pinfunction "1_1") (pintype "passive"))
      (node (ref "COMML") (pin "4") (pinfunction "4_4") (pintype "passive"))
    )
    (net (code "138") (name "Net-(CCOMLP-Pad2)") (class "Default")
      (node (ref "CCOMLP") (pin "2") (pinfunction "2_2") (pintype "passive"))
      (node (ref "D1") (pin "2") (pinfunction "2_2") (pintype "bidirectional"))
      (node (ref "RCOML") (pin "1") (pinfunction "1_1") (pintype "passive"))
    )
    (net (code "139") (name "Net-(CISOL-Pad2)") (class "Default")
      (node (ref "CISOL") (pin "2") (pinfunction "2_2") (pintype "passive"))
      (node (ref "RCOMH") (pin "1") (pinfunction "1_1") (pintype "passive"))
    )
    (net (code "140") (name "Net-(CISOL1-Pad2)") (class "Default")
      (node (ref "CISOL1") (pin "2") (pinfunction "2_2") (pintype "passive"))
      (node (ref "RCOMH1") (pin "1") (pinfunction "1_1") (pintype "passive"))
    )
    (net (code "141") (name "Net-(CNPN-1-Pad2)") (class "Default")
      (node (ref "CNPN-1") (pin "2") (pinfunction "2_2") (pintype "passive"))
      (node (ref "RNPN-1") (pin "2") (pinfunction "2_2") (pintype "passive"))
      (node (ref "T2") (pin "C") (pinfunction "C_C") (pintype "passive"))
    )
    (net (code "142") (name "Net-(CNPN-Pad2)") (class "Default")
      (node (ref "CNPN") (pin "2") (pinfunction "2_2") (pintype "passive"))
      (node (ref "RNPN") (pin "2") (pinfunction "2_2") (pintype "passive"))
      (node (ref "T1") (pin "C") (pinfunction "C_C") (pintype "passive"))
    )
    (net (code "143") (name "Net-(IC1-NEG5V)") (class "Default")
      (node (ref "CNEG5V-1") (pin "1") (pinfunction "1_1") (pintype "passive"))
      (node (ref "IC1") (pin "44") (pinfunction "NEG5V_44") (pintype "bidirectional"))
    )
    (net (code "144") (name "Net-(IC2-NEG5V)") (class "Default")
      (node (ref "CNEG5V") (pin "1") (pinfunction "1_1") (pintype "passive"))
      (node (ref "IC2") (pin "44") (pinfunction "NEG5V_44") (pintype "bidirectional"))
    )
    (net (code "145") (name "unconnected-(COMMH-Pad1)") (class "Default")
      (node (ref "COMMH") (pin "1") (pinfunction "1_1") (pintype "passive"))
    )
    (net (code "146") (name "unconnected-(COMMH-Pad3)") (class "Default")
      (node (ref "COMMH") (pin "3") (pinfunction "3_3") (pintype "passive"))
    )
    (net (code "147") (name "unconnected-(COMML-Pad1)") (class "Default")
      (node (ref "COMML") (pin "1") (pinfunction "1_1") (pintype "passive"))
    )
    (net (code "148") (name "unconnected-(COMML-Pad3)") (class "Default")
      (node (ref "COMML") (pin "3") (pinfunction "3_3") (pintype "passive"))
    )
    (net (code "149") (name "unconnected-(IC1-BBN(SRN)-Pad63)") (class "Default")
      (node (ref "IC1") (pin "63") (pinfunction "BBN(SRN)_63") (pintype "bidirectional"))
    )
    (net (code "150") (name "unconnected-(IC1-BBP(SRP)-Pad64)") (class "Default")
      (node (ref "IC1") (pin "64") (pinfunction "BBP(SRP)_64") (pintype "bidirectional"))
    )
    (net (code "151") (name "unconnected-(IC1-TX-Pad53)") (class "Default")
      (node (ref "IC1") (pin "53") (pinfunction "TX_53") (pintype "bidirectional"))
    )
    (net (code "152") (name "unconnected-(SR-Pad1)") (class "Default")
      (node (ref "SR") (pin "1") (pinfunction "1_1") (pintype "passive"))
    )
    (net (code "153") (name "unconnected-(SR-Pad2)") (class "Default")
      (node (ref "SR") (pin "2") (pinfunction "2_2") (pintype "passive"))
    )
  )
)
